# io-board-c-8.net
KiCad netlist of a schematic drawn in EAGLE
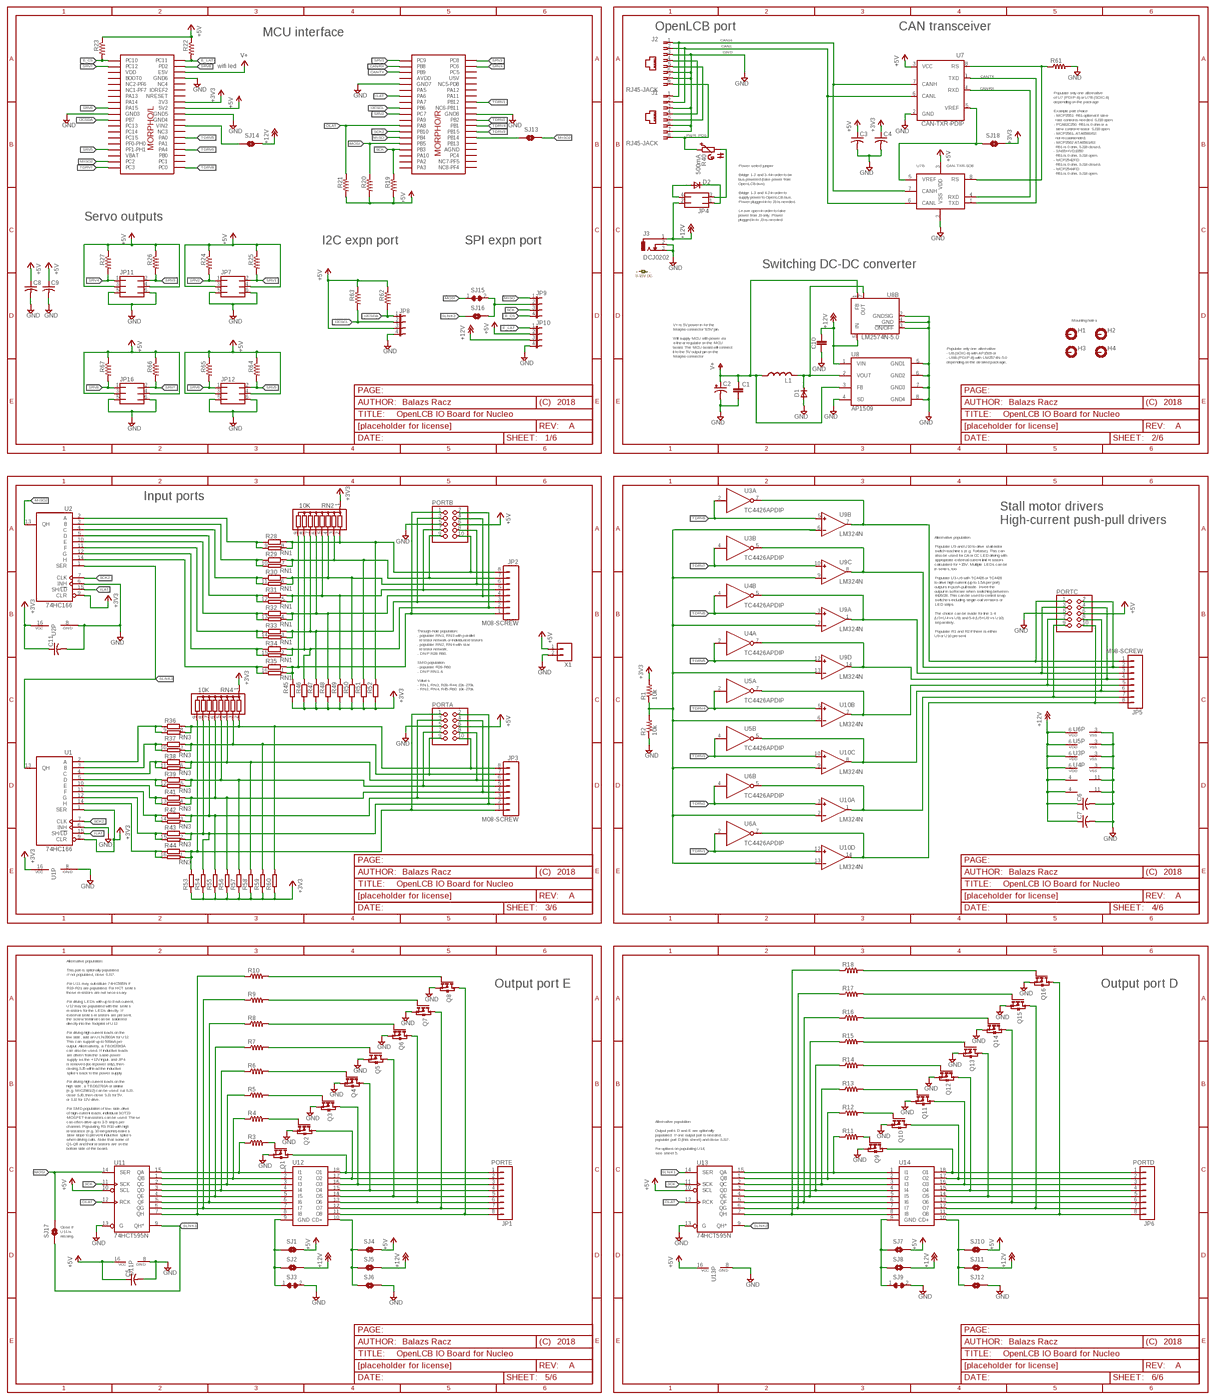
[diagram p0: schematic, sheet 1, overview]
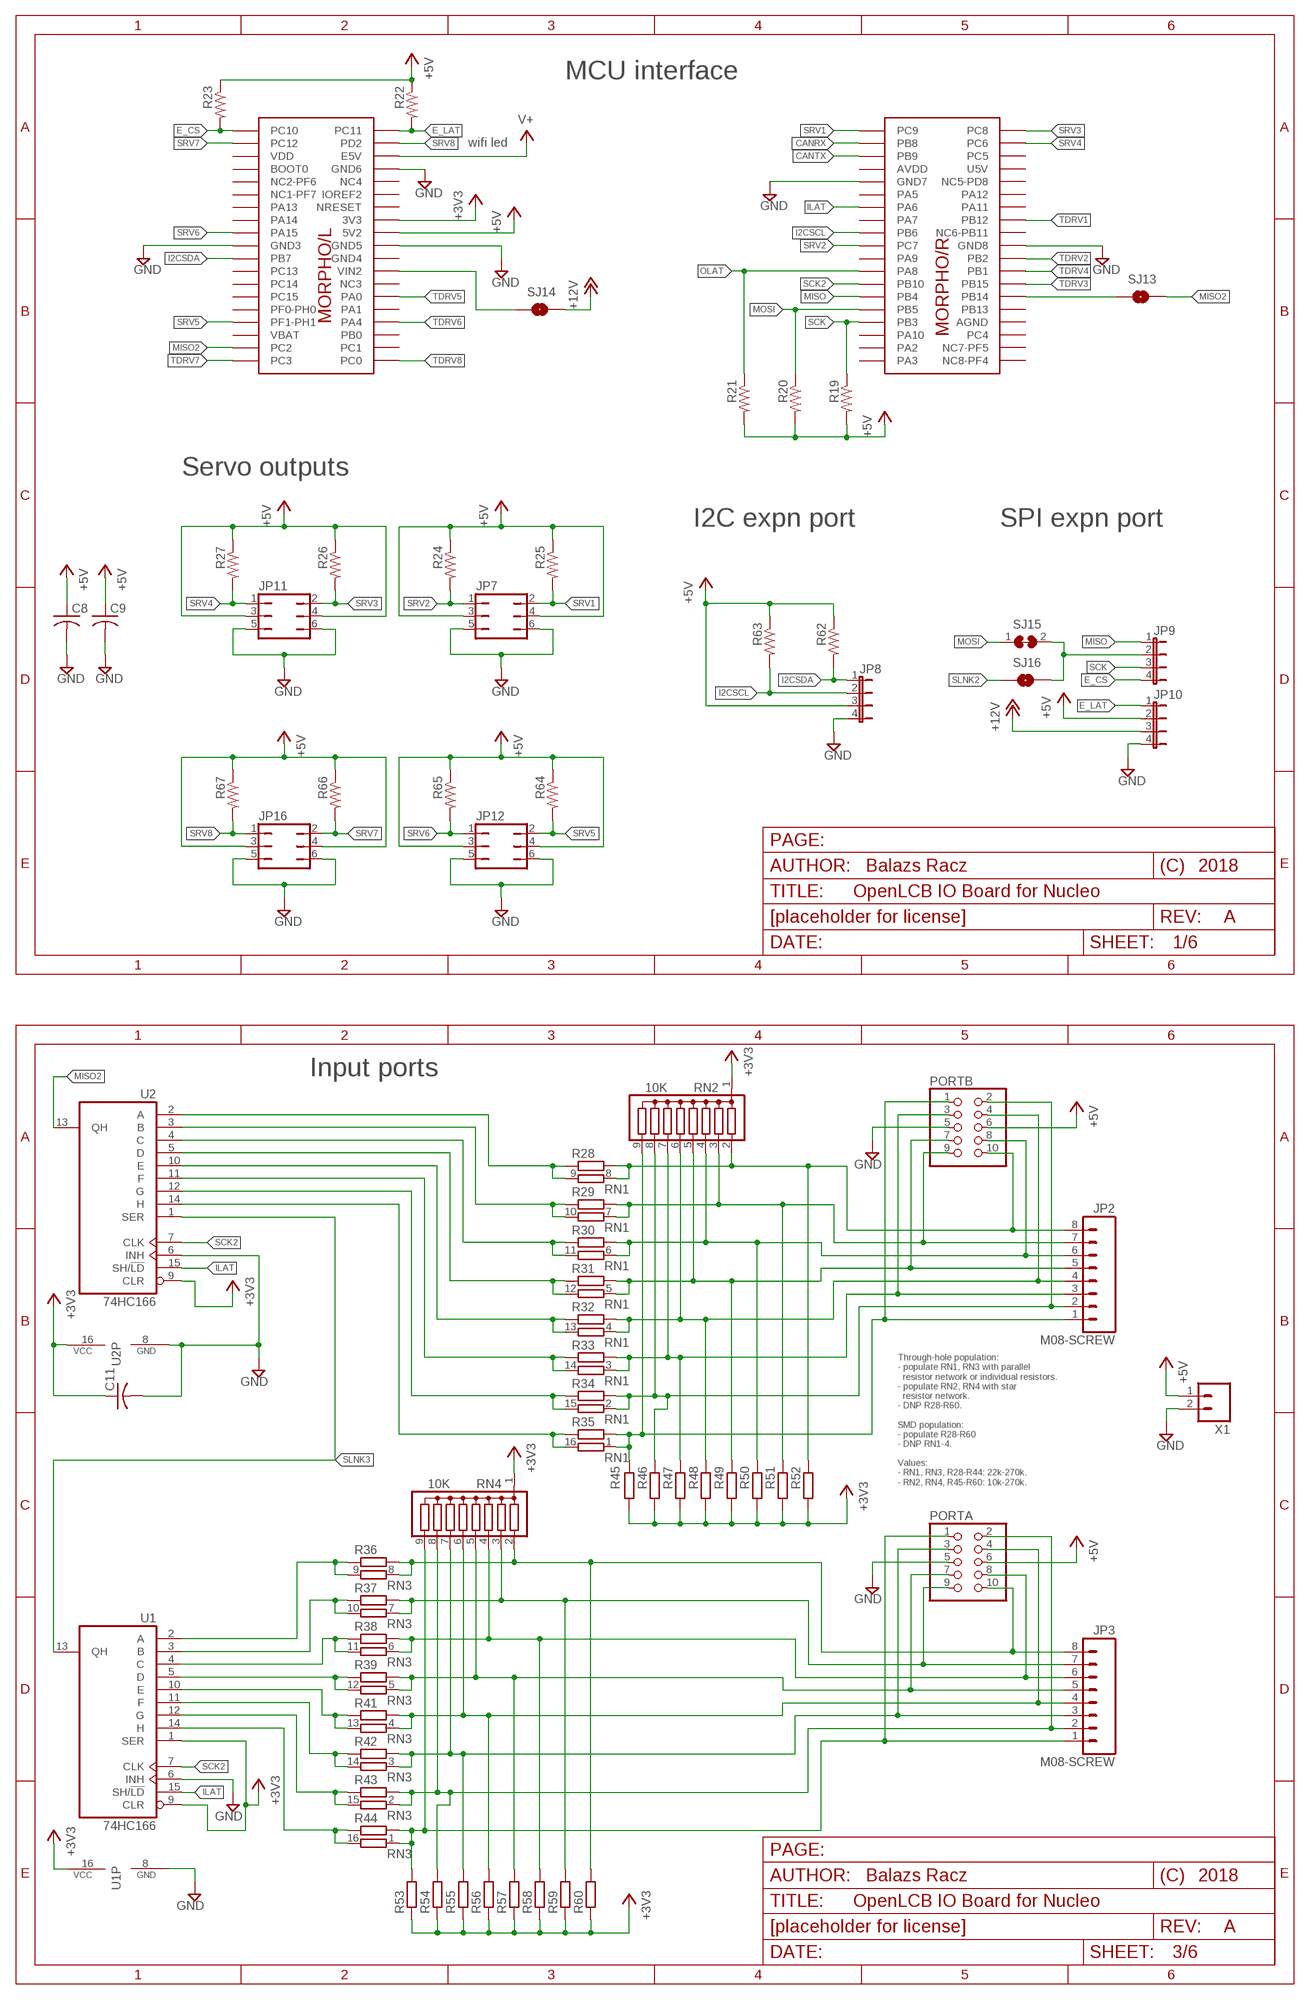
[diagram p1: schematic, sheet 1, part 1 of 4]
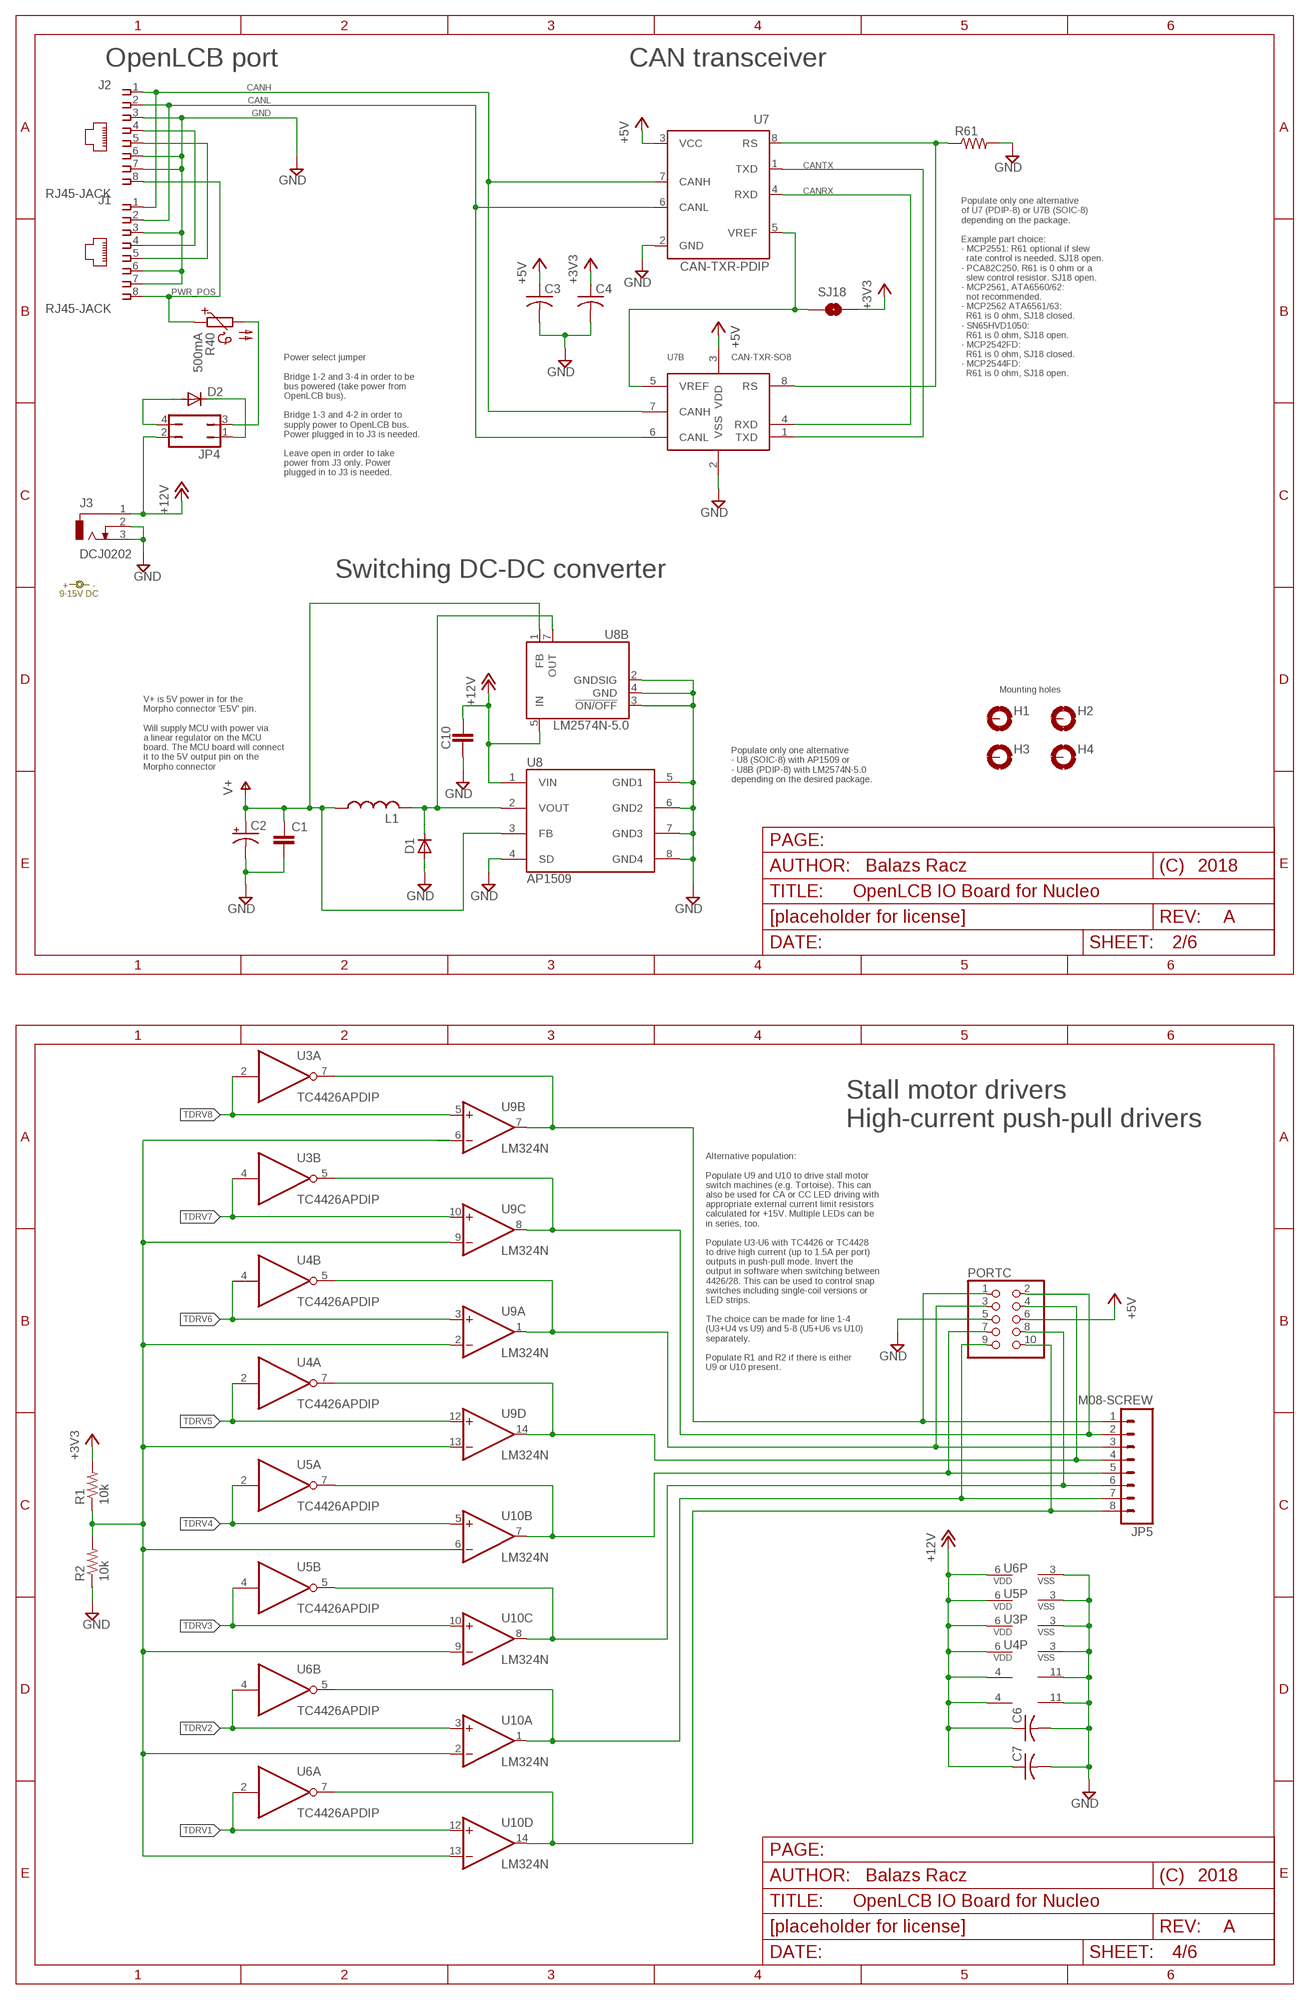
[diagram p2: schematic, sheet 1, part 2 of 4]
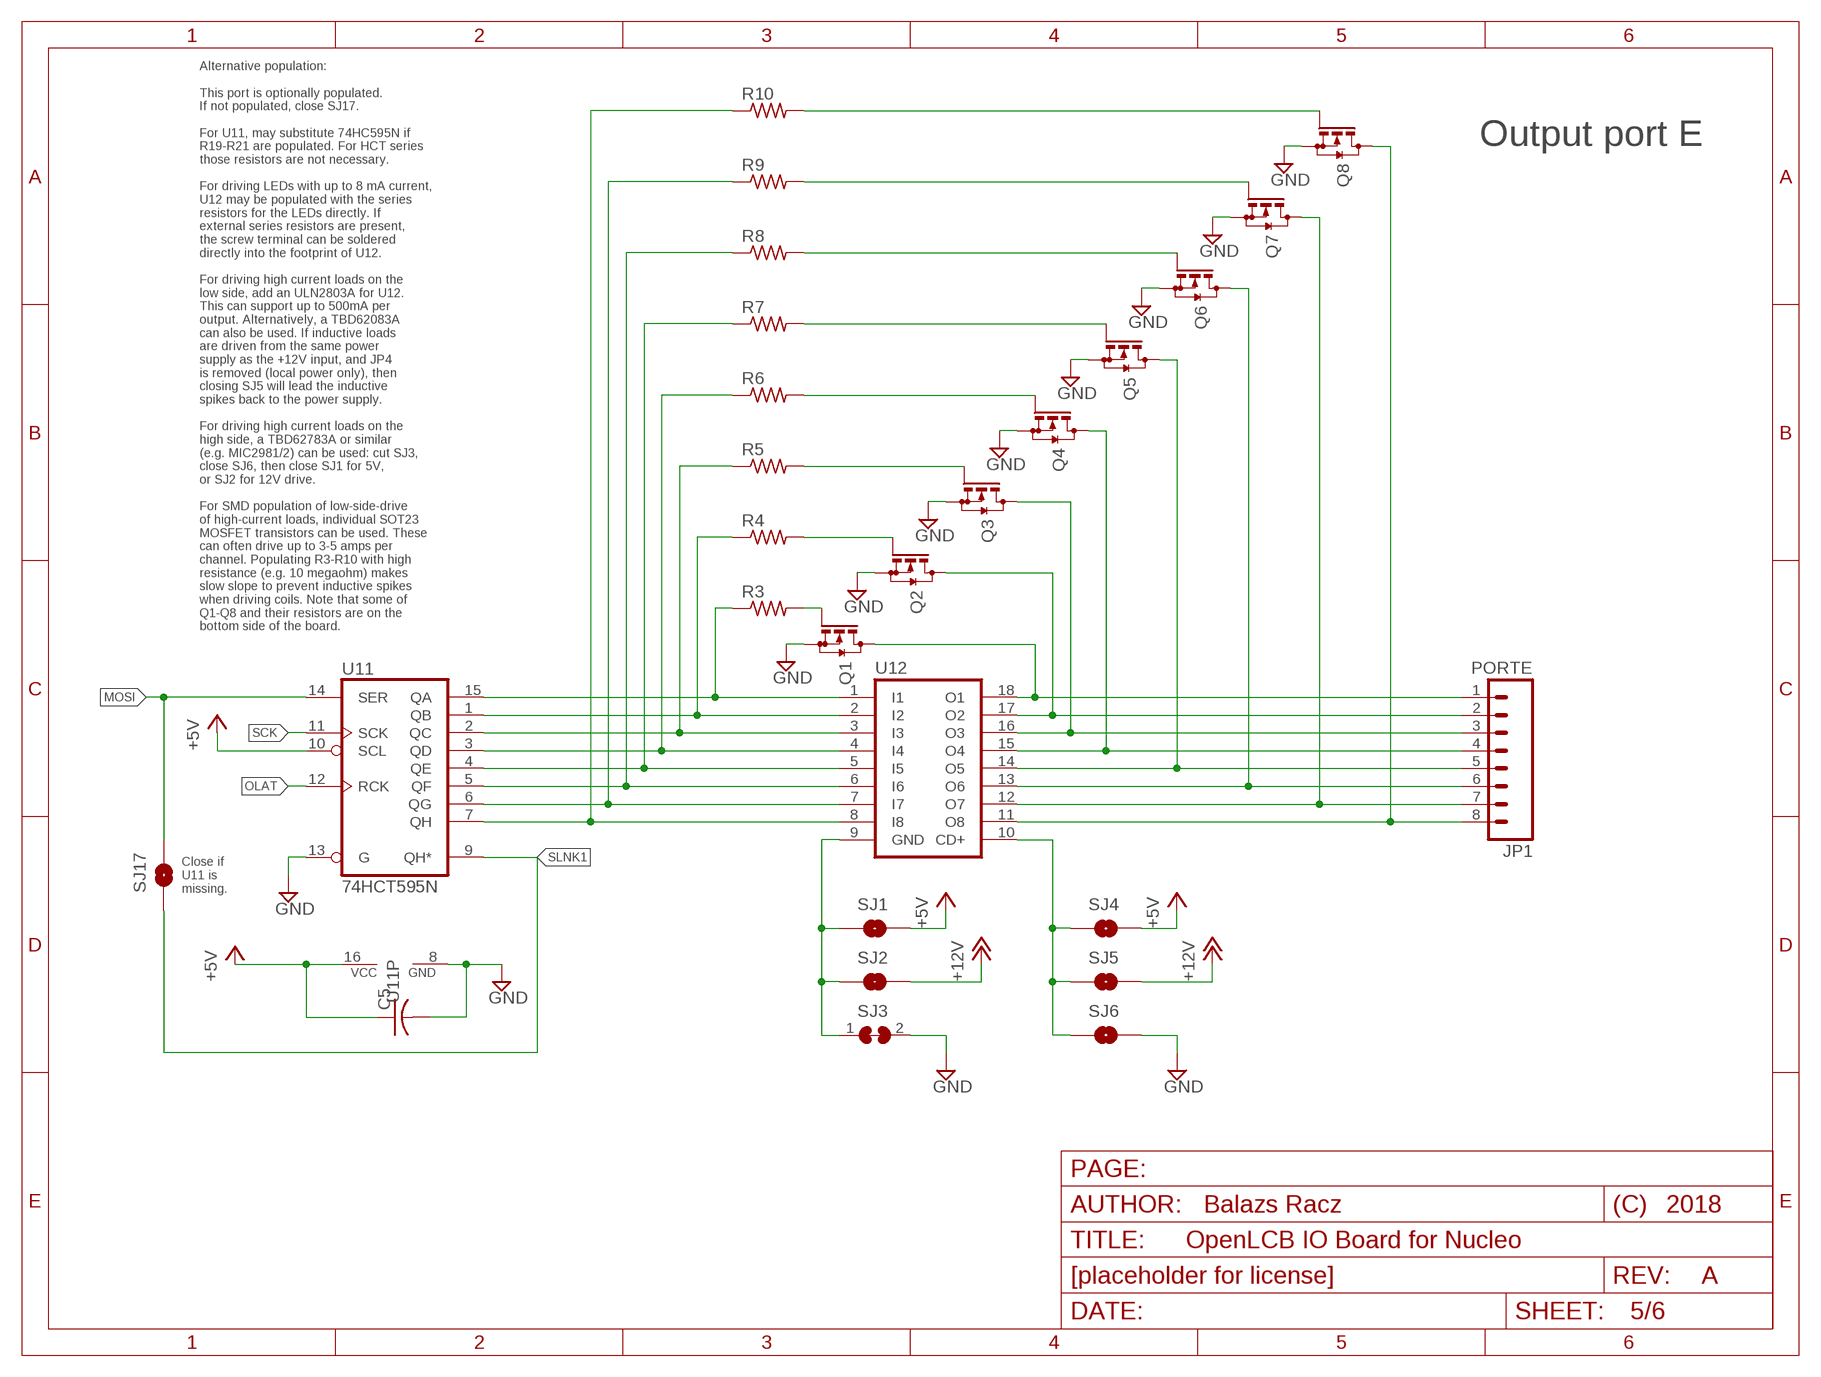
[diagram p3: schematic, sheet 1, part 3 of 4]
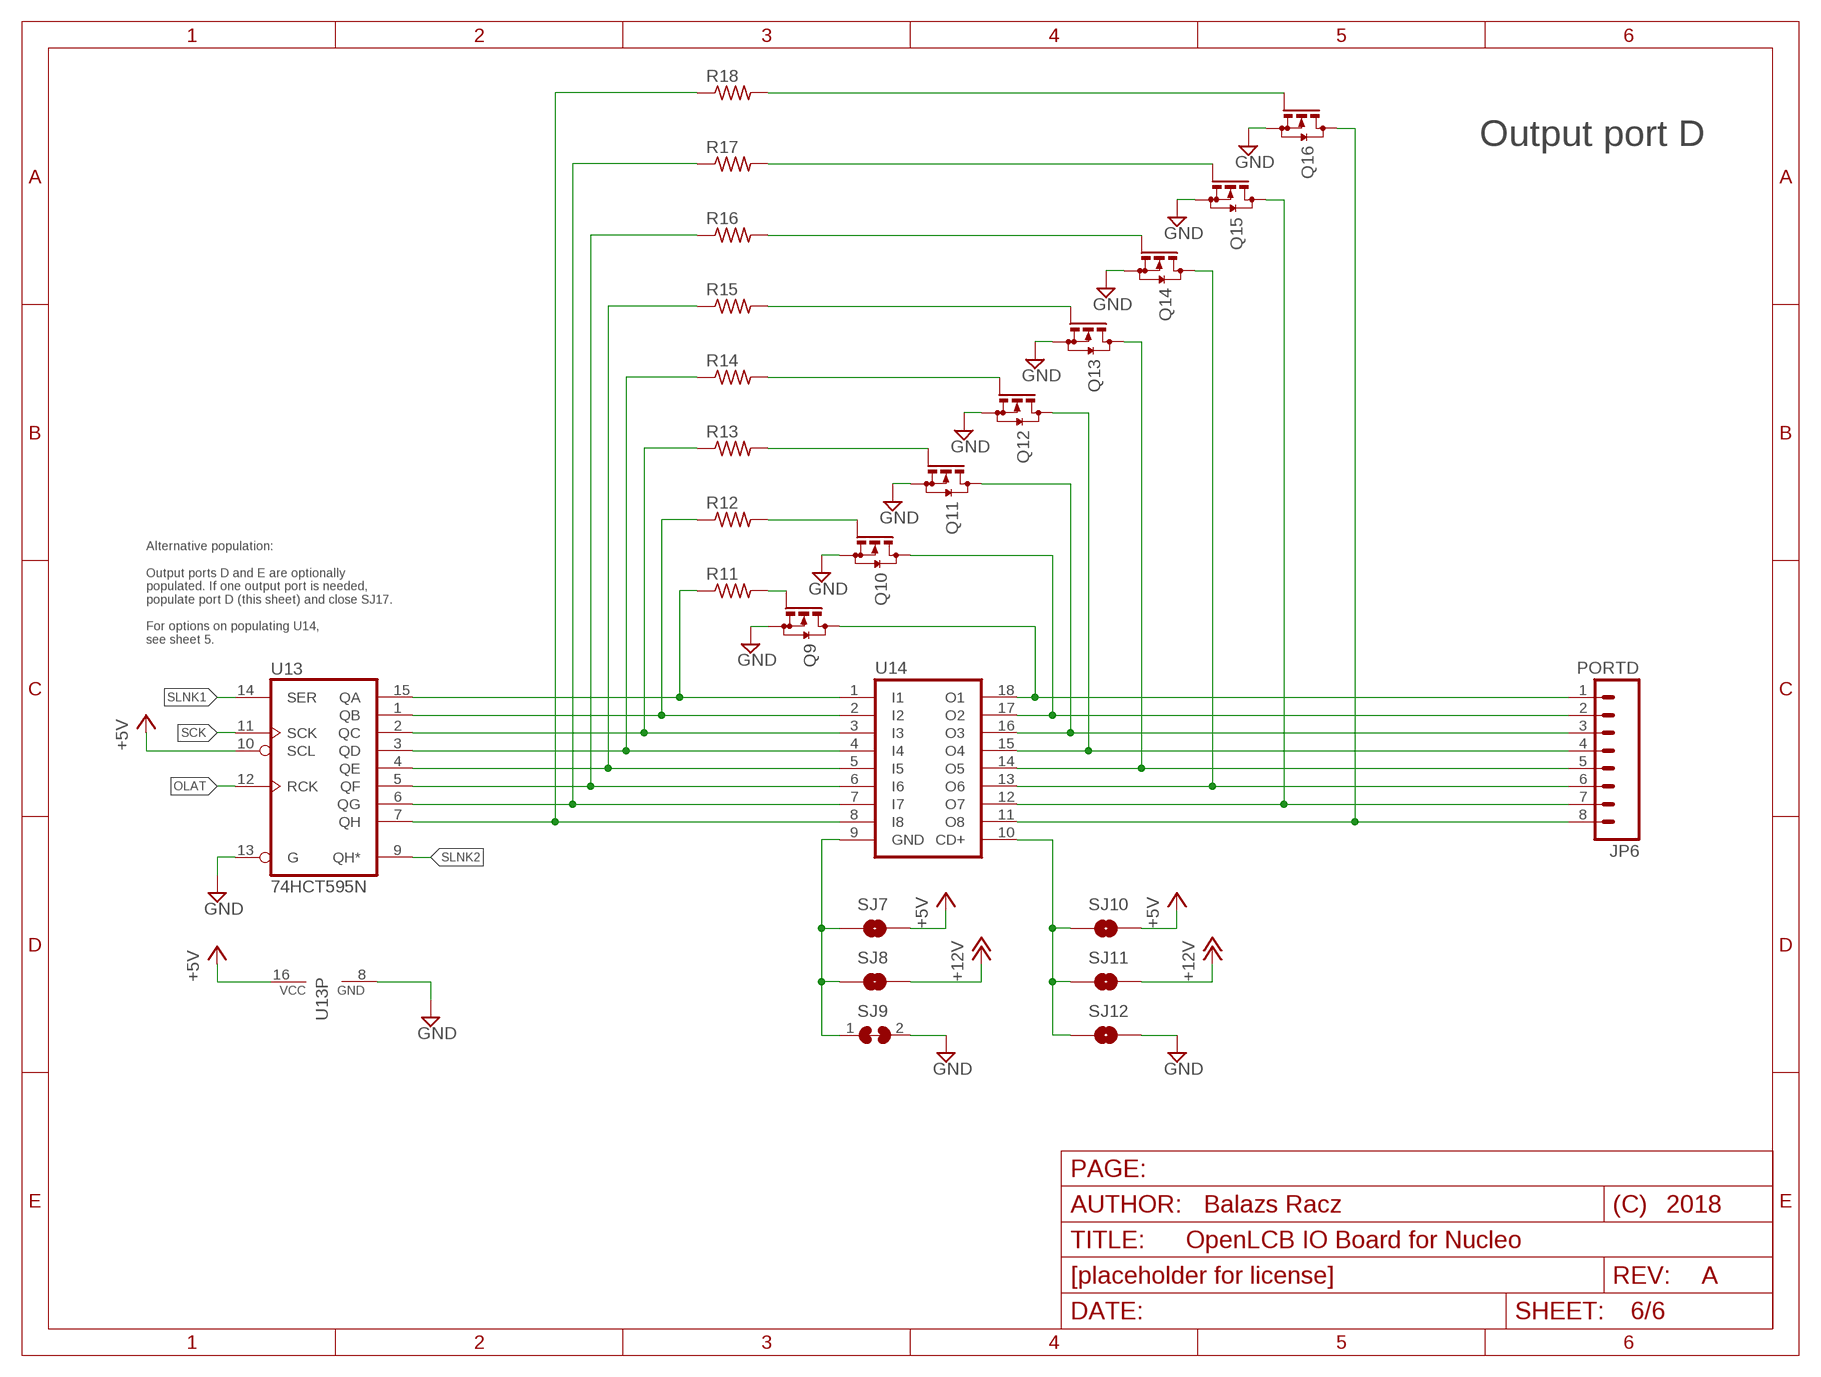
[diagram p4: schematic, sheet 1, part 4 of 4]

(export (version "E")
  (design (tool "Eeschema 10.0.6"))
  (components
    (comp (ref "+12V")
      (value "9-15V DC")
      (footprint "eagle-import:POWER_USAGE")
      (libsource (lib "eagle-import") (part "DOC-POWER_LABEL"))
    )
    (comp (ref "C1")
      (value "C-EUC1206")
      (footprint "eagle-import:C1206")
      (libsource (lib "eagle-import") (part "C-EUC1206"))
    )
    (comp (ref "C2")
      (value "CPOL-USE2.5-5")
      (footprint "eagle-import:E2,5-5")
      (libsource (lib "eagle-import") (part "CPOL-USE2.5-5"))
    )
    (comp (ref "C3")
      (value "C-USC0805")
      (footprint "eagle-import:C0805")
      (libsource (lib "eagle-import") (part "C-USC0805"))
    )
    (comp (ref "C4")
      (value "C-USC0805")
      (footprint "eagle-import:C0805")
      (libsource (lib "eagle-import") (part "C-USC0805"))
    )
    (comp (ref "C5")
      (value "C-USC0805")
      (footprint "eagle-import:C0805")
      (libsource (lib "eagle-import") (part "C-USC0805"))
    )
    (comp (ref "C6")
      (value "C-USC1206")
      (footprint "eagle-import:C1206")
      (libsource (lib "eagle-import") (part "C-USC1206"))
    )
    (comp (ref "C7")
      (value "C-USC1206")
      (footprint "eagle-import:C1206")
      (libsource (lib "eagle-import") (part "C-USC1206"))
    )
    (comp (ref "C8")
      (value "C-USC1206")
      (footprint "eagle-import:C1206")
      (libsource (lib "eagle-import") (part "C-USC1206"))
    )
    (comp (ref "C9")
      (value "C-USC1206")
      (footprint "eagle-import:C1206")
      (libsource (lib "eagle-import") (part "C-USC1206"))
    )
    (comp (ref "C10")
      (value "C-EUC1206")
      (footprint "eagle-import:C1206")
      (libsource (lib "eagle-import") (part "C-EUC1206"))
    )
    (comp (ref "C11")
      (value "C-USC0805")
      (footprint "eagle-import:C0805")
      (libsource (lib "eagle-import") (part "C-USC0805"))
    )
    (comp (ref "D1")
      (value "DIODE-DO41-7.6")
      (footprint "eagle-import:DO41-7.6")
      (libsource (lib "eagle-import") (part "DIODE-DO41-7.6"))
    )
    (comp (ref "D2")
      (value "DIODE-DO41-7.6")
      (footprint "eagle-import:DO41-7.6")
      (libsource (lib "eagle-import") (part "DIODE-DO41-7.6"))
    )
    (comp (ref "H1")
      (value "MOUNT-PAD-ROUND3.3")
      (footprint "eagle-import:3,3-PAD")
      (libsource (lib "eagle-import") (part "MOUNT-PAD-ROUND3.3"))
    )
    (comp (ref "H2")
      (value "MOUNT-PAD-ROUND3.3")
      (footprint "eagle-import:3,3-PAD")
      (libsource (lib "eagle-import") (part "MOUNT-PAD-ROUND3.3"))
    )
    (comp (ref "H3")
      (value "MOUNT-PAD-ROUND3.3")
      (footprint "eagle-import:3,3-PAD")
      (libsource (lib "eagle-import") (part "MOUNT-PAD-ROUND3.3"))
    )
    (comp (ref "H4")
      (value "MOUNT-PAD-ROUND3.3")
      (footprint "eagle-import:3,3-PAD")
      (libsource (lib "eagle-import") (part "MOUNT-PAD-ROUND3.3"))
    )
    (comp (ref "J1")
      (value "RJ45-JACK")
      (footprint "eagle-import:RJ45-PULSE-E5J88")
      (libsource (lib "eagle-import") (part "RJ45-JACKRJ45-PULSE-E5J00"))
    )
    (comp (ref "J2")
      (value "RJ45-JACK")
      (footprint "eagle-import:RJ45-PULSE-E5J88")
      (libsource (lib "eagle-import") (part "RJ45-JACKRJ45-PULSE-E5J00"))
    )
    (comp (ref "J3")
      (value "DCJ0202")
      (footprint "eagle-import:DCJ0202")
      (libsource (lib "eagle-import") (part "DCJ0202"))
    )
    (comp (ref "JP1")
      (value "PORTE")
      (footprint "eagle-import:1X08_TERMINAL")
      (libsource (lib "eagle-import") (part "M08-SCREW"))
    )
    (comp (ref "JP2")
      (value "M08-SCREW")
      (footprint "eagle-import:1X08_TERMINAL")
      (libsource (lib "eagle-import") (part "M08-SCREW"))
    )
    (comp (ref "JP3")
      (value "M08-SCREW")
      (footprint "eagle-import:1X08_TERMINAL")
      (libsource (lib "eagle-import") (part "M08-SCREW"))
    )
    (comp (ref "JP4")
      (value "JP2Q")
      (footprint "eagle-import:JP2Q")
      (libsource (lib "eagle-import") (part "JP2Q"))
    )
    (comp (ref "JP5")
      (value "M08-SCREW")
      (footprint "eagle-import:1X08_TERMINAL")
      (libsource (lib "eagle-import") (part "M08-SCREW"))
    )
    (comp (ref "JP6")
      (value "PORTD")
      (footprint "eagle-import:1X08_TERMINAL")
      (libsource (lib "eagle-import") (part "M08-SCREW"))
    )
    (comp (ref "JP7")
      (value "JP3Q")
      (footprint "eagle-import:JP3Q")
      (libsource (lib "eagle-import") (part "JP3Q"))
    )
    (comp (ref "JP8")
      (value "JP4-FLAT")
      (footprint "eagle-import:JP4F")
      (libsource (lib "eagle-import") (part "JP4-FLAT"))
    )
    (comp (ref "JP9")
      (value "JP4-FLAT")
      (footprint "eagle-import:JP4F")
      (libsource (lib "eagle-import") (part "JP4-FLAT"))
    )
    (comp (ref "JP10")
      (value "JP4-FLAT")
      (footprint "eagle-import:JP4F")
      (libsource (lib "eagle-import") (part "JP4-FLAT"))
    )
    (comp (ref "JP11")
      (value "JP3Q")
      (footprint "eagle-import:JP3Q")
      (libsource (lib "eagle-import") (part "JP3Q"))
    )
    (comp (ref "JP12")
      (value "JP3Q")
      (footprint "eagle-import:JP3Q")
      (libsource (lib "eagle-import") (part "JP3Q"))
    )
    (comp (ref "JP16")
      (value "JP3Q")
      (footprint "eagle-import:JP3Q")
      (libsource (lib "eagle-import") (part "JP3Q"))
    )
    (comp (ref "L1")
      (value "L-US")
      (footprint "eagle-import:L5-8,5")
      (libsource (lib "eagle-import") (part "L-US"))
    )
    (comp (ref "PORTA")
      (value "PINHD-2X5CN")
      (footprint "eagle-import:CON10M")
      (libsource (lib "eagle-import") (part "PINHD-2X5CN"))
    )
    (comp (ref "PORTB")
      (value "PINHD-2X5CN")
      (footprint "eagle-import:CON10M")
      (libsource (lib "eagle-import") (part "PINHD-2X5CN"))
    )
    (comp (ref "PORTC")
      (value "PINHD-2X5CN")
      (footprint "eagle-import:CON10M")
      (libsource (lib "eagle-import") (part "PINHD-2X5CN"))
    )
    (comp (ref "Q1")
      (value "BSS123")
      (footprint "eagle-import:SOT23")
      (libsource (lib "eagle-import") (part "BSS123"))
    )
    (comp (ref "Q2")
      (value "BSS123")
      (footprint "eagle-import:SOT23")
      (libsource (lib "eagle-import") (part "BSS123"))
    )
    (comp (ref "Q3")
      (value "BSS123")
      (footprint "eagle-import:SOT23")
      (libsource (lib "eagle-import") (part "BSS123"))
    )
    (comp (ref "Q4")
      (value "BSS123")
      (footprint "eagle-import:SOT23")
      (libsource (lib "eagle-import") (part "BSS123"))
    )
    (comp (ref "Q5")
      (value "BSS123")
      (footprint "eagle-import:SOT23")
      (libsource (lib "eagle-import") (part "BSS123"))
    )
    (comp (ref "Q6")
      (value "BSS123")
      (footprint "eagle-import:SOT23")
      (libsource (lib "eagle-import") (part "BSS123"))
    )
    (comp (ref "Q7")
      (value "BSS123")
      (footprint "eagle-import:SOT23")
      (libsource (lib "eagle-import") (part "BSS123"))
    )
    (comp (ref "Q8")
      (value "BSS123")
      (footprint "eagle-import:SOT23")
      (libsource (lib "eagle-import") (part "BSS123"))
    )
    (comp (ref "Q9")
      (value "BSS123")
      (footprint "eagle-import:SOT23")
      (libsource (lib "eagle-import") (part "BSS123"))
    )
    (comp (ref "Q10")
      (value "BSS123")
      (footprint "eagle-import:SOT23")
      (libsource (lib "eagle-import") (part "BSS123"))
    )
    (comp (ref "Q11")
      (value "BSS123")
      (footprint "eagle-import:SOT23")
      (libsource (lib "eagle-import") (part "BSS123"))
    )
    (comp (ref "Q12")
      (value "BSS123")
      (footprint "eagle-import:SOT23")
      (libsource (lib "eagle-import") (part "BSS123"))
    )
    (comp (ref "Q13")
      (value "BSS123")
      (footprint "eagle-import:SOT23")
      (libsource (lib "eagle-import") (part "BSS123"))
    )
    (comp (ref "Q14")
      (value "BSS123")
      (footprint "eagle-import:SOT23")
      (libsource (lib "eagle-import") (part "BSS123"))
    )
    (comp (ref "Q15")
      (value "BSS123")
      (footprint "eagle-import:SOT23")
      (libsource (lib "eagle-import") (part "BSS123"))
    )
    (comp (ref "Q16")
      (value "BSS123")
      (footprint "eagle-import:SOT23")
      (libsource (lib "eagle-import") (part "BSS123"))
    )
    (comp (ref "R1")
      (value "10k")
      (footprint "eagle-import:R0805")
      (libsource (lib "eagle-import") (part "R-US_R0805"))
    )
    (comp (ref "R2")
      (value "10k")
      (footprint "eagle-import:R0805")
      (libsource (lib "eagle-import") (part "R-US_R0805"))
    )
    (comp (ref "R3")
      (value "R-US_R0603")
      (footprint "eagle-import:R0603")
      (libsource (lib "eagle-import") (part "R-US_R0603"))
    )
    (comp (ref "R4")
      (value "R-US_R0603")
      (footprint "eagle-import:R0603")
      (libsource (lib "eagle-import") (part "R-US_R0603"))
    )
    (comp (ref "R5")
      (value "R-US_R0603")
      (footprint "eagle-import:R0603")
      (libsource (lib "eagle-import") (part "R-US_R0603"))
    )
    (comp (ref "R6")
      (value "R-US_R0603")
      (footprint "eagle-import:R0603")
      (libsource (lib "eagle-import") (part "R-US_R0603"))
    )
    (comp (ref "R7")
      (value "R-US_R0603")
      (footprint "eagle-import:R0603")
      (libsource (lib "eagle-import") (part "R-US_R0603"))
    )
    (comp (ref "R8")
      (value "R-US_R0603")
      (footprint "eagle-import:R0603")
      (libsource (lib "eagle-import") (part "R-US_R0603"))
    )
    (comp (ref "R9")
      (value "R-US_R0603")
      (footprint "eagle-import:R0603")
      (libsource (lib "eagle-import") (part "R-US_R0603"))
    )
    (comp (ref "R10")
      (value "R-US_R0603")
      (footprint "eagle-import:R0603")
      (libsource (lib "eagle-import") (part "R-US_R0603"))
    )
    (comp (ref "R11")
      (value "R-US_R0603")
      (footprint "eagle-import:R0603")
      (libsource (lib "eagle-import") (part "R-US_R0603"))
    )
    (comp (ref "R12")
      (value "R-US_R0603")
      (footprint "eagle-import:R0603")
      (libsource (lib "eagle-import") (part "R-US_R0603"))
    )
    (comp (ref "R13")
      (value "R-US_R0603")
      (footprint "eagle-import:R0603")
      (libsource (lib "eagle-import") (part "R-US_R0603"))
    )
    (comp (ref "R14")
      (value "R-US_R0603")
      (footprint "eagle-import:R0603")
      (libsource (lib "eagle-import") (part "R-US_R0603"))
    )
    (comp (ref "R15")
      (value "R-US_R0603")
      (footprint "eagle-import:R0603")
      (libsource (lib "eagle-import") (part "R-US_R0603"))
    )
    (comp (ref "R16")
      (value "R-US_R0603")
      (footprint "eagle-import:R0603")
      (libsource (lib "eagle-import") (part "R-US_R0603"))
    )
    (comp (ref "R17")
      (value "R-US_R0603")
      (footprint "eagle-import:R0603")
      (libsource (lib "eagle-import") (part "R-US_R0603"))
    )
    (comp (ref "R18")
      (value "R-US_R0603")
      (footprint "eagle-import:R0603")
      (libsource (lib "eagle-import") (part "R-US_R0603"))
    )
    (comp (ref "R19")
      (value "R-US_R0805")
      (footprint "eagle-import:R0805")
      (libsource (lib "eagle-import") (part "rcl_334_R-US_R0805"))
    )
    (comp (ref "R20")
      (value "R-US_R0805")
      (footprint "eagle-import:R0805")
      (libsource (lib "eagle-import") (part "rcl_334_R-US_R0805"))
    )
    (comp (ref "R21")
      (value "R-US_R0805")
      (footprint "eagle-import:R0805")
      (libsource (lib "eagle-import") (part "rcl_334_R-US_R0805"))
    )
    (comp (ref "R22")
      (value "R-US_R0805")
      (footprint "eagle-import:R0805")
      (libsource (lib "eagle-import") (part "rcl_334_R-US_R0805"))
    )
    (comp (ref "R23")
      (value "R-US_R0805")
      (footprint "eagle-import:R0805")
      (libsource (lib "eagle-import") (part "rcl_334_R-US_R0805"))
    )
    (comp (ref "R24")
      (value "R-US_R0805")
      (footprint "eagle-import:R0805")
      (libsource (lib "eagle-import") (part "rcl_334_R-US_R0805"))
    )
    (comp (ref "R25")
      (value "R-US_R0805")
      (footprint "eagle-import:R0805")
      (libsource (lib "eagle-import") (part "rcl_334_R-US_R0805"))
    )
    (comp (ref "R26")
      (value "R-US_R0805")
      (footprint "eagle-import:R0805")
      (libsource (lib "eagle-import") (part "rcl_334_R-US_R0805"))
    )
    (comp (ref "R27")
      (value "R-US_R0805")
      (footprint "eagle-import:R0805")
      (libsource (lib "eagle-import") (part "rcl_334_R-US_R0805"))
    )
    (comp (ref "R28")
      (value "R-EU_R0603")
      (footprint "eagle-import:R0603")
      (libsource (lib "eagle-import") (part "R-EU_R0603"))
    )
    (comp (ref "R29")
      (value "R-EU_R0603")
      (footprint "eagle-import:R0603")
      (libsource (lib "eagle-import") (part "R-EU_R0603"))
    )
    (comp (ref "R30")
      (value "R-EU_R0603")
      (footprint "eagle-import:R0603")
      (libsource (lib "eagle-import") (part "R-EU_R0603"))
    )
    (comp (ref "R31")
      (value "R-EU_R0603")
      (footprint "eagle-import:R0603")
      (libsource (lib "eagle-import") (part "R-EU_R0603"))
    )
    (comp (ref "R32")
      (value "R-EU_R0603")
      (footprint "eagle-import:R0603")
      (libsource (lib "eagle-import") (part "R-EU_R0603"))
    )
    (comp (ref "R33")
      (value "R-EU_R0603")
      (footprint "eagle-import:R0603")
      (libsource (lib "eagle-import") (part "R-EU_R0603"))
    )
    (comp (ref "R34")
      (value "R-EU_R0603")
      (footprint "eagle-import:R0603")
      (libsource (lib "eagle-import") (part "R-EU_R0603"))
    )
    (comp (ref "R35")
      (value "R-EU_R0603")
      (footprint "eagle-import:R0603")
      (libsource (lib "eagle-import") (part "R-EU_R0603"))
    )
    (comp (ref "R36")
      (value "R-EU_R0603")
      (footprint "eagle-import:R0603")
      (libsource (lib "eagle-import") (part "R-EU_R0603"))
    )
    (comp (ref "R37")
      (value "R-EU_R0603")
      (footprint "eagle-import:R0603")
      (libsource (lib "eagle-import") (part "R-EU_R0603"))
    )
    (comp (ref "R38")
      (value "R-EU_R0603")
      (footprint "eagle-import:R0603")
      (libsource (lib "eagle-import") (part "R-EU_R0603"))
    )
    (comp (ref "R39")
      (value "R-EU_R0603")
      (footprint "eagle-import:R0603")
      (libsource (lib "eagle-import") (part "R-EU_R0603"))
    )
    (comp (ref "R40")
      (value "500mA")
      (footprint "eagle-import:PTC1812")
      (libsource (lib "eagle-import") (part "PTC_1812"))
    )
    (comp (ref "R41")
      (value "R-EU_R0603")
      (footprint "eagle-import:R0603")
      (libsource (lib "eagle-import") (part "R-EU_R0603"))
    )
    (comp (ref "R42")
      (value "R-EU_R0603")
      (footprint "eagle-import:R0603")
      (libsource (lib "eagle-import") (part "R-EU_R0603"))
    )
    (comp (ref "R43")
      (value "R-EU_R0603")
      (footprint "eagle-import:R0603")
      (libsource (lib "eagle-import") (part "R-EU_R0603"))
    )
    (comp (ref "R44")
      (value "R-EU_R0603")
      (footprint "eagle-import:R0603")
      (libsource (lib "eagle-import") (part "R-EU_R0603"))
    )
    (comp (ref "R45")
      (value "R-EU_R0603")
      (footprint "eagle-import:R0603")
      (libsource (lib "eagle-import") (part "R-EU_R0603"))
    )
    (comp (ref "R46")
      (value "R-EU_R0603")
      (footprint "eagle-import:R0603")
      (libsource (lib "eagle-import") (part "R-EU_R0603"))
    )
    (comp (ref "R47")
      (value "R-EU_R0603")
      (footprint "eagle-import:R0603")
      (libsource (lib "eagle-import") (part "R-EU_R0603"))
    )
    (comp (ref "R48")
      (value "R-EU_R0603")
      (footprint "eagle-import:R0603")
      (libsource (lib "eagle-import") (part "R-EU_R0603"))
    )
    (comp (ref "R49")
      (value "R-EU_R0603")
      (footprint "eagle-import:R0603")
      (libsource (lib "eagle-import") (part "R-EU_R0603"))
    )
    (comp (ref "R50")
      (value "R-EU_R0603")
      (footprint "eagle-import:R0603")
      (libsource (lib "eagle-import") (part "R-EU_R0603"))
    )
    (comp (ref "R51")
      (value "R-EU_R0603")
      (footprint "eagle-import:R0603")
      (libsource (lib "eagle-import") (part "R-EU_R0603"))
    )
    (comp (ref "R52")
      (value "R-EU_R0603")
      (footprint "eagle-import:R0603")
      (libsource (lib "eagle-import") (part "R-EU_R0603"))
    )
    (comp (ref "R53")
      (value "R-EU_R0603")
      (footprint "eagle-import:R0603")
      (libsource (lib "eagle-import") (part "R-EU_R0603"))
    )
    (comp (ref "R54")
      (value "R-EU_R0603")
      (footprint "eagle-import:R0603")
      (libsource (lib "eagle-import") (part "R-EU_R0603"))
    )
    (comp (ref "R55")
      (value "R-EU_R0603")
      (footprint "eagle-import:R0603")
      (libsource (lib "eagle-import") (part "R-EU_R0603"))
    )
    (comp (ref "R56")
      (value "R-EU_R0603")
      (footprint "eagle-import:R0603")
      (libsource (lib "eagle-import") (part "R-EU_R0603"))
    )
    (comp (ref "R57")
      (value "R-EU_R0603")
      (footprint "eagle-import:R0603")
      (libsource (lib "eagle-import") (part "R-EU_R0603"))
    )
    (comp (ref "R58")
      (value "R-EU_R0603")
      (footprint "eagle-import:R0603")
      (libsource (lib "eagle-import") (part "R-EU_R0603"))
    )
    (comp (ref "R59")
      (value "R-EU_R0603")
      (footprint "eagle-import:R0603")
      (libsource (lib "eagle-import") (part "R-EU_R0603"))
    )
    (comp (ref "R60")
      (value "R-EU_R0603")
      (footprint "eagle-import:R0603")
      (libsource (lib "eagle-import") (part "R-EU_R0603"))
    )
    (comp (ref "R61")
      (value "R-US_R0805")
      (footprint "eagle-import:R0805")
      (libsource (lib "eagle-import") (part "rcl_334_R-US_R0805"))
    )
    (comp (ref "R62")
      (value "R-US_R0805")
      (footprint "eagle-import:R0805")
      (libsource (lib "eagle-import") (part "rcl_334_R-US_R0805"))
    )
    (comp (ref "R63")
      (value "R-US_R0805")
      (footprint "eagle-import:R0805")
      (libsource (lib "eagle-import") (part "rcl_334_R-US_R0805"))
    )
    (comp (ref "R64")
      (value "R-US_R0805")
      (footprint "eagle-import:R0805")
      (libsource (lib "eagle-import") (part "rcl_334_R-US_R0805"))
    )
    (comp (ref "R65")
      (value "R-US_R0805")
      (footprint "eagle-import:R0805")
      (libsource (lib "eagle-import") (part "rcl_334_R-US_R0805"))
    )
    (comp (ref "R66")
      (value "R-US_R0805")
      (footprint "eagle-import:R0805")
      (libsource (lib "eagle-import") (part "rcl_334_R-US_R0805"))
    )
    (comp (ref "R67")
      (value "R-US_R0805")
      (footprint "eagle-import:R0805")
      (libsource (lib "eagle-import") (part "rcl_334_R-US_R0805"))
    )
    (comp (ref "RN1")
      (value "8R-P")
      (footprint "eagle-import:DIL16")
      (libsource (lib "eagle-import") (part "8R-P"))
    )
    (comp (ref "RN2")
      (value "10K")
      (footprint "eagle-import:SIL9")
      (libsource (lib "eagle-import") (part "G08R"))
    )
    (comp (ref "RN3")
      (value "8R-P")
      (footprint "eagle-import:DIL16")
      (libsource (lib "eagle-import") (part "8R-P"))
    )
    (comp (ref "RN4")
      (value "10K")
      (footprint "eagle-import:SIL9")
      (libsource (lib "eagle-import") (part "G08R"))
    )
    (comp (ref "SJ1")
      (value "SJRND2")
      (footprint "eagle-import:SJ_RND2")
      (libsource (lib "eagle-import") (part "SJRND2"))
    )
    (comp (ref "SJ2")
      (value "SJRND2")
      (footprint "eagle-import:SJ_RND2")
      (libsource (lib "eagle-import") (part "SJRND2"))
    )
    (comp (ref "SJ3")
      (value "SJ-C")
      (footprint "eagle-import:SJW-C")
      (libsource (lib "eagle-import") (part "SJ-C"))
    )
    (comp (ref "SJ4")
      (value "SJRND2")
      (footprint "eagle-import:SJ_RND2")
      (libsource (lib "eagle-import") (part "SJRND2"))
    )
    (comp (ref "SJ5")
      (value "SJRND2")
      (footprint "eagle-import:SJ_RND2")
      (libsource (lib "eagle-import") (part "SJRND2"))
    )
    (comp (ref "SJ6")
      (value "SJRND2")
      (footprint "eagle-import:SJ_RND2")
      (libsource (lib "eagle-import") (part "SJRND2"))
    )
    (comp (ref "SJ7")
      (value "SJRND2")
      (footprint "eagle-import:SJ_RND2")
      (libsource (lib "eagle-import") (part "SJRND2"))
    )
    (comp (ref "SJ8")
      (value "SJRND2")
      (footprint "eagle-import:SJ_RND2")
      (libsource (lib "eagle-import") (part "SJRND2"))
    )
    (comp (ref "SJ9")
      (value "SJ-C")
      (footprint "eagle-import:SJW-C")
      (libsource (lib "eagle-import") (part "SJ-C"))
    )
    (comp (ref "SJ10")
      (value "SJRND2")
      (footprint "eagle-import:SJ_RND2")
      (libsource (lib "eagle-import") (part "SJRND2"))
    )
    (comp (ref "SJ11")
      (value "SJRND2")
      (footprint "eagle-import:SJ_RND2")
      (libsource (lib "eagle-import") (part "SJRND2"))
    )
    (comp (ref "SJ12")
      (value "SJRND2")
      (footprint "eagle-import:SJ_RND2")
      (libsource (lib "eagle-import") (part "SJRND2"))
    )
    (comp (ref "SJ13")
      (value "SJRND2")
      (footprint "eagle-import:SJ_RND2")
      (libsource (lib "eagle-import") (part "SJRND2"))
    )
    (comp (ref "SJ14")
      (value "SJRND2")
      (footprint "eagle-import:SJ_RND2")
      (libsource (lib "eagle-import") (part "SJRND2"))
    )
    (comp (ref "SJ15")
      (value "SJ-C")
      (footprint "eagle-import:SJW-C")
      (libsource (lib "eagle-import") (part "SJ-C"))
    )
    (comp (ref "SJ16")
      (value "SJRND2")
      (footprint "eagle-import:SJ_RND2")
      (libsource (lib "eagle-import") (part "SJRND2"))
    )
    (comp (ref "SJ17")
      (value "SJRND2")
      (footprint "eagle-import:SJ_RND2")
      (libsource (lib "eagle-import") (part "SJRND2"))
    )
    (comp (ref "SJ18")
      (value "SJRND2")
      (footprint "eagle-import:SJ_RND2")
      (libsource (lib "eagle-import") (part "SJRND2"))
    )
    (comp (ref "U$1")
      (value "NUCLEO_64_GENERIC")
      (footprint "eagle-import:NUCLEO_BRD_BASE64")
      (libsource (lib "eagle-import") (part "NUCLEO_64_GENERIC"))
    )
    (comp (ref "U1")
      (value "74HC166")
      (footprint "eagle-import:DIL16")
      (libsource (lib "eagle-import") (part "74166N"))
    )
    (comp (ref "U2")
      (value "74HC166")
      (footprint "eagle-import:DIL16")
      (libsource (lib "eagle-import") (part "74166N"))
    )
    (comp (ref "U3")
      (value "TC4426APDIP")
      (footprint "eagle-import:DIL08-LONG")
      (libsource (lib "eagle-import") (part "TC4426APDIP"))
    )
    (comp (ref "U4")
      (value "TC4426APDIP")
      (footprint "eagle-import:DIL08-LONG")
      (libsource (lib "eagle-import") (part "TC4426APDIP"))
    )
    (comp (ref "U5")
      (value "TC4426APDIP")
      (footprint "eagle-import:DIL08-LONG")
      (libsource (lib "eagle-import") (part "TC4426APDIP"))
    )
    (comp (ref "U6")
      (value "TC4426APDIP")
      (footprint "eagle-import:DIL08-LONG")
      (libsource (lib "eagle-import") (part "TC4426APDIP"))
    )
    (comp (ref "U7")
      (value "CAN-TXR-PDIP")
      (footprint "eagle-import:DIL08")
      (libsource (lib "eagle-import") (part "PCA82C250"))
    )
    (comp (ref "U7B")
      (value "CAN-TXR-SO8")
      (footprint "eagle-import:SO-08")
      (libsource (lib "eagle-import") (part "MCP2551-SN"))
    )
    (comp (ref "U8")
      (value "AP1509")
      (footprint "eagle-import:SO-08")
      (libsource (lib "eagle-import") (part "AP1509"))
    )
    (comp (ref "U8B")
      (value "LM2574N-5.0")
      (footprint "eagle-import:DIL08")
      (libsource (lib "eagle-import") (part "LM2574?-N5.0"))
    )
    (comp (ref "U9")
      (value "LM324N")
      (footprint "eagle-import:DIL14")
      (libsource (lib "eagle-import") (part "LM324N"))
    )
    (comp (ref "U10")
      (value "LM324N")
      (footprint "eagle-import:DIL14")
      (libsource (lib "eagle-import") (part "LM324N"))
    )
    (comp (ref "U11")
      (value "74HCT595N")
      (footprint "eagle-import:DIL16")
      (libsource (lib "eagle-import") (part "74595NHCT"))
    )
    (comp (ref "U12")
      (value "ULN2803A")
      (footprint "eagle-import:DIL18-THIN")
      (libsource (lib "eagle-import") (part "ULN2803A"))
    )
    (comp (ref "U13")
      (value "74HCT595N")
      (footprint "eagle-import:DIL16")
      (libsource (lib "eagle-import") (part "74595NHCT"))
    )
    (comp (ref "U14")
      (value "ULN2803A")
      (footprint "eagle-import:DIL18-THIN")
      (libsource (lib "eagle-import") (part "ULN2803A"))
    )
    (comp (ref "X1")
      (value "CONNECTOR-M023.5MM-LOCK")
      (footprint "eagle-import:SCREWTERMINAL-3.5MM-2_LOCK")
      (libsource (lib "eagle-import") (part "CONNECTOR-M023.5MM-LOCK"))
    )
  )
  (nets
    (net (code "1") (name "+3V3") (class "Default")
      (node (ref "C11") (pin "1") (pinfunction "1_1") (pintype "passive"))
      (node (ref "C4") (pin "1") (pinfunction "1_1") (pintype "passive"))
      (node (ref "R1") (pin "2") (pinfunction "2_2") (pintype "passive"))
      (node (ref "R45") (pin "1") (pinfunction "1_1") (pintype "passive"))
      (node (ref "R46") (pin "2") (pinfunction "2_2") (pintype "passive"))
      (node (ref "R47") (pin "2") (pinfunction "2_2") (pintype "passive"))
      (node (ref "R48") (pin "2") (pinfunction "2_2") (pintype "passive"))
      (node (ref "R49") (pin "2") (pinfunction "2_2") (pintype "passive"))
      (node (ref "R50") (pin "2") (pinfunction "2_2") (pintype "passive"))
      (node (ref "R51") (pin "2") (pinfunction "2_2") (pintype "passive"))
      (node (ref "R52") (pin "2") (pinfunction "2_2") (pintype "passive"))
      (node (ref "R53") (pin "1") (pinfunction "1_1") (pintype "passive"))
      (node (ref "R54") (pin "1") (pinfunction "1_1") (pintype "passive"))
      (node (ref "R55") (pin "1") (pinfunction "1_1") (pintype "passive"))
      (node (ref "R56") (pin "1") (pinfunction "1_1") (pintype "passive"))
      (node (ref "R57") (pin "1") (pinfunction "1_1") (pintype "passive"))
      (node (ref "R58") (pin "1") (pinfunction "1_1") (pintype "passive"))
      (node (ref "R59") (pin "1") (pinfunction "1_1") (pintype "passive"))
      (node (ref "R60") (pin "1") (pinfunction "1_1") (pintype "passive"))
      (node (ref "RN2") (pin "1") (pinfunction "1_1") (pintype "passive"))
      (node (ref "RN4") (pin "1") (pinfunction "1_1") (pintype "passive"))
      (node (ref "SJ18") (pin "P$1") (pinfunction "1_P$1") (pintype "passive"))
      (node (ref "U$1") (pin "3V3") (pinfunction "3V3_3V3") (pintype "power_in"))
      (node (ref "U1") (pin "1") (pinfunction "SER_1") (pintype "input"))
      (node (ref "U1") (pin "16") (pinfunction "VCC_16") (pintype "power_in"))
      (node (ref "U1") (pin "9") (pinfunction "CLR_9") (pintype "input"))
      (node (ref "U2") (pin "16") (pinfunction "VCC_16") (pintype "power_in"))
      (node (ref "U2") (pin "9") (pinfunction "CLR_9") (pintype "input"))
    )
    (net (code "2") (name "+5V") (class "Default")
      (node (ref "C3") (pin "1") (pinfunction "1_1") (pintype "passive"))
      (node (ref "C5") (pin "1") (pinfunction "1_1") (pintype "passive"))
      (node (ref "C8") (pin "1") (pinfunction "1_1") (pintype "passive"))
      (node (ref "C9") (pin "1") (pinfunction "1_1") (pintype "passive"))
      (node (ref "JP10") (pin "2") (pinfunction "2_2") (pintype "passive"))
      (node (ref "JP11") (pin "3") (pinfunction "3_3") (pintype "passive"))
      (node (ref "JP11") (pin "4") (pinfunction "4_4") (pintype "passive"))
      (node (ref "JP12") (pin "3") (pinfunction "3_3") (pintype "passive"))
      (node (ref "JP12") (pin "4") (pinfunction "4_4") (pintype "passive"))
      (node (ref "JP16") (pin "3") (pinfunction "3_3") (pintype "passive"))
      (node (ref "JP16") (pin "4") (pinfunction "4_4") (pintype "passive"))
      (node (ref "JP7") (pin "3") (pinfunction "3_3") (pintype "passive"))
      (node (ref "JP7") (pin "4") (pinfunction "4_4") (pintype "passive"))
      (node (ref "JP8") (pin "3") (pinfunction "3_3") (pintype "passive"))
      (node (ref "PORTA") (pin "6") (pinfunction "6_6") (pintype "passive"))
      (node (ref "PORTB") (pin "6") (pinfunction "6_6") (pintype "passive"))
      (node (ref "PORTC") (pin "6") (pinfunction "6_6") (pintype "passive"))
      (node (ref "R19") (pin "2") (pinfunction "2_2") (pintype "passive"))
      (node (ref "R20") (pin "2") (pinfunction "2_2") (pintype "passive"))
      (node (ref "R21") (pin "2") (pinfunction "2_2") (pintype "passive"))
      (node (ref "R22") (pin "1") (pinfunction "1_1") (pintype "passive"))
      (node (ref "R23") (pin "1") (pinfunction "1_1") (pintype "passive"))
      (node (ref "R24") (pin "1") (pinfunction "1_1") (pintype "passive"))
      (node (ref "R25") (pin "1") (pinfunction "1_1") (pintype "passive"))
      (node (ref "R26") (pin "1") (pinfunction "1_1") (pintype "passive"))
      (node (ref "R27") (pin "1") (pinfunction "1_1") (pintype "passive"))
      (node (ref "R62") (pin "1") (pinfunction "1_1") (pintype "passive"))
      (node (ref "R63") (pin "1") (pinfunction "1_1") (pintype "passive"))
      (node (ref "R64") (pin "1") (pinfunction "1_1") (pintype "passive"))
      (node (ref "R65") (pin "1") (pinfunction "1_1") (pintype "passive"))
      (node (ref "R66") (pin "1") (pinfunction "1_1") (pintype "passive"))
      (node (ref "R67") (pin "1") (pinfunction "1_1") (pintype "passive"))
      (node (ref "SJ1") (pin "P$2") (pinfunction "2_P$2") (pintype "passive"))
      (node (ref "SJ10") (pin "P$2") (pinfunction "2_P$2") (pintype "passive"))
      (node (ref "SJ4") (pin "P$2") (pinfunction "2_P$2") (pintype "passive"))
      (node (ref "SJ7") (pin "P$2") (pinfunction "2_P$2") (pintype "passive"))
      (node (ref "U$1") (pin "5V2") (pinfunction "5V2_5V2") (pintype "power_in"))
      (node (ref "U11") (pin "10") (pinfunction "SCL_10") (pintype "input"))
      (node (ref "U11") (pin "16") (pinfunction "VCC_16") (pintype "power_in"))
      (node (ref "U13") (pin "10") (pinfunction "SCL_10") (pintype "input"))
      (node (ref "U13") (pin "16") (pinfunction "VCC_16") (pintype "power_in"))
      (node (ref "U7") (pin "3") (pinfunction "VCC_3") (pintype "power_in"))
      (node (ref "U7B") (pin "3") (pinfunction "VDD_3") (pintype "power_in"))
      (node (ref "X1") (pin "1") (pinfunction "1_1") (pintype "passive"))
    )
    (net (code "3") (name "+12V") (class "Default")
      (node (ref "C10") (pin "1") (pinfunction "1_1") (pintype "passive"))
      (node (ref "C6") (pin "1") (pinfunction "1_1") (pintype "passive"))
      (node (ref "C7") (pin "1") (pinfunction "1_1") (pintype "passive"))
      (node (ref "J3") (pin "1") (pinfunction "1_1") (pintype "passive"))
      (node (ref "JP10") (pin "3") (pinfunction "3_3") (pintype "passive"))
      (node (ref "JP4") (pin "2") (pinfunction "2_2") (pintype "passive"))
      (node (ref "SJ11") (pin "P$2") (pinfunction "2_P$2") (pintype "passive"))
      (node (ref "SJ14") (pin "P$2") (pinfunction "2_P$2") (pintype "passive"))
      (node (ref "SJ2") (pin "P$2") (pinfunction "2_P$2") (pintype "passive"))
      (node (ref "SJ5") (pin "P$2") (pinfunction "2_P$2") (pintype "passive"))
      (node (ref "SJ8") (pin "P$2") (pinfunction "2_P$2") (pintype "passive"))
      (node (ref "U10") (pin "4") (pinfunction "V+_4") (pintype "power_in"))
      (node (ref "U3") (pin "6") (pinfunction "VDD_6") (pintype "power_in"))
      (node (ref "U4") (pin "6") (pinfunction "VDD_6") (pintype "power_in"))
      (node (ref "U5") (pin "6") (pinfunction "VDD_6") (pintype "power_in"))
      (node (ref "U6") (pin "6") (pinfunction "VDD_6") (pintype "power_in"))
      (node (ref "U8") (pin "1") (pinfunction "VIN_1") (pintype "bidirectional"))
      (node (ref "U8B") (pin "5") (pinfunction "IN_5") (pintype "input"))
      (node (ref "U9") (pin "4") (pinfunction "V+_4") (pintype "power_in"))
    )
    (net (code "4") (name "/AGND") (class "Default")
      (node (ref "U$1") (pin "AGND") (pinfunction "AGND_AGND") (pintype "power_in"))
    )
    (net (code "5") (name "/AVDD") (class "Default")
      (node (ref "U$1") (pin "AVDD") (pinfunction "AVDD_AVDD") (pintype "power_in"))
    )
    (net (code "6") (name "/CANH") (class "Default")
      (node (ref "J1") (pin "1") (pinfunction "1_1") (pintype "passive"))
      (node (ref "J2") (pin "1") (pinfunction "1_1") (pintype "passive"))
      (node (ref "U7") (pin "7") (pinfunction "CANH_7") (pintype "bidirectional"))
      (node (ref "U7B") (pin "7") (pinfunction "CANH_7") (pintype "bidirectional"))
    )
    (net (code "7") (name "/CANL") (class "Default")
      (node (ref "J1") (pin "2") (pinfunction "2_2") (pintype "passive"))
      (node (ref "J2") (pin "2") (pinfunction "2_2") (pintype "passive"))
      (node (ref "U7") (pin "6") (pinfunction "CANL_6") (pintype "bidirectional"))
      (node (ref "U7B") (pin "6") (pinfunction "CANL_6") (pintype "bidirectional"))
    )
    (net (code "8") (name "/GND4") (class "Default")
      (node (ref "U$1") (pin "GND4") (pinfunction "GND4_GND4") (pintype "power_in"))
    )
    (net (code "9") (name "/PWR_POS") (class "Default")
      (node (ref "J1") (pin "8") (pinfunction "8_8") (pintype "passive"))
      (node (ref "J2") (pin "8") (pinfunction "8_8") (pintype "passive"))
      (node (ref "R40") (pin "1") (pinfunction "1_1") (pintype "passive"))
    )
    (net (code "10") (name "/U5V") (class "Default")
      (node (ref "U$1") (pin "U5V") (pinfunction "U5V_U5V") (pintype "power_in"))
    )
    (net (code "11") (name "/VBAT") (class "Default")
      (node (ref "U$1") (pin "VBAT") (pinfunction "VBAT_VBAT") (pintype "power_in"))
    )
    (net (code "12") (name "/VDD") (class "Default")
      (node (ref "U$1") (pin "VDD") (pinfunction "VDD_VDD") (pintype "power_in"))
    )
    (net (code "13") (name "CANRX") (class "Default")
      (node (ref "U$1") (pin "PB8") (pinfunction "PB8_PB8") (pintype "bidirectional"))
      (node (ref "U7") (pin "4") (pinfunction "RXD_4") (pintype "output"))
      (node (ref "U7B") (pin "4") (pinfunction "RXD_4") (pintype "bidirectional"))
    )
    (net (code "14") (name "CANTX") (class "Default")
      (node (ref "U$1") (pin "PB9") (pinfunction "PB9_PB9") (pintype "bidirectional"))
      (node (ref "U7") (pin "1") (pinfunction "TXD_1") (pintype "input"))
      (node (ref "U7B") (pin "1") (pinfunction "TXD_1") (pintype "bidirectional"))
    )
    (net (code "15") (name "E_CS") (class "Default")
      (node (ref "JP9") (pin "4") (pinfunction "4_4") (pintype "passive"))
      (node (ref "R23") (pin "2") (pinfunction "2_2") (pintype "passive"))
      (node (ref "U$1") (pin "PC10") (pinfunction "PC10_PC10") (pintype "bidirectional"))
    )
    (net (code "16") (name "E_LAT") (class "Default")
      (node (ref "JP10") (pin "1") (pinfunction "1_1") (pintype "passive"))
      (node (ref "R22") (pin "2") (pinfunction "2_2") (pintype "passive"))
      (node (ref "U$1") (pin "PC11") (pinfunction "PC11_PC11") (pintype "bidirectional"))
    )
    (net (code "17") (name "GND") (class "Default")
      (node (ref "C1") (pin "2") (pinfunction "2_2") (pintype "passive"))
      (node (ref "C10") (pin "2") (pinfunction "2_2") (pintype "passive"))
      (node (ref "C11") (pin "2") (pinfunction "2_2") (pintype "passive"))
      (node (ref "C2") (pin "-") (pinfunction "-_-") (pintype "passive"))
      (node (ref "C3") (pin "2") (pinfunction "2_2") (pintype "passive"))
      (node (ref "C4") (pin "2") (pinfunction "2_2") (pintype "passive"))
      (node (ref "C5") (pin "2") (pinfunction "2_2") (pintype "passive"))
      (node (ref "C6") (pin "2") (pinfunction "2_2") (pintype "passive"))
      (node (ref "C7") (pin "2") (pinfunction "2_2") (pintype "passive"))
      (node (ref "C8") (pin "2") (pinfunction "2_2") (pintype "passive"))
      (node (ref "C9") (pin "2") (pinfunction "2_2") (pintype "passive"))
      (node (ref "D1") (pin "A") (pinfunction "A_A") (pintype "passive"))
      (node (ref "J1") (pin "3") (pinfunction "3_3") (pintype "passive"))
      (node (ref "J1") (pin "6") (pinfunction "6_6") (pintype "passive"))
      (node (ref "J1") (pin "7") (pinfunction "7_7") (pintype "passive"))
      (node (ref "J2") (pin "3") (pinfunction "3_3") (pintype "passive"))
      (node (ref "J2") (pin "6") (pinfunction "6_6") (pintype "passive"))
      (node (ref "J2") (pin "7") (pinfunction "7_7") (pintype "passive"))
      (node (ref "J3") (pin "2") (pinfunction "2_2") (pintype "passive"))
      (node (ref "J3") (pin "3") (pinfunction "3_3") (pintype "passive"))
      (node (ref "JP10") (pin "4") (pinfunction "4_4") (pintype "passive"))
      (node (ref "JP11") (pin "5") (pinfunction "5_5") (pintype "passive"))
      (node (ref "JP11") (pin "6") (pinfunction "6_6") (pintype "passive"))
      (node (ref "JP12") (pin "5") (pinfunction "5_5") (pintype "passive"))
      (node (ref "JP12") (pin "6") (pinfunction "6_6") (pintype "passive"))
      (node (ref "JP16") (pin "5") (pinfunction "5_5") (pintype "passive"))
      (node (ref "JP16") (pin "6") (pinfunction "6_6") (pintype "passive"))
      (node (ref "JP7") (pin "5") (pinfunction "5_5") (pintype "passive"))
      (node (ref "JP7") (pin "6") (pinfunction "6_6") (pintype "passive"))
      (node (ref "JP8") (pin "4") (pinfunction "4_4") (pintype "passive"))
      (node (ref "PORTA") (pin "5") (pinfunction "5_5") (pintype "passive"))
      (node (ref "PORTB") (pin "5") (pinfunction "5_5") (pintype "passive"))
      (node (ref "PORTC") (pin "5") (pinfunction "5_5") (pintype "passive"))
      (node (ref "Q1") (pin "2") (pinfunction "S_2") (pintype "passive"))
      (node (ref "Q10") (pin "2") (pinfunction "S_2") (pintype "passive"))
      (node (ref "Q11") (pin "2") (pinfunction "S_2") (pintype "passive"))
      (node (ref "Q12") (pin "2") (pinfunction "S_2") (pintype "passive"))
      (node (ref "Q13") (pin "2") (pinfunction "S_2") (pintype "passive"))
      (node (ref "Q14") (pin "2") (pinfunction "S_2") (pintype "passive"))
      (node (ref "Q15") (pin "2") (pinfunction "S_2") (pintype "passive"))
      (node (ref "Q16") (pin "2") (pinfunction "S_2") (pintype "passive"))
      (node (ref "Q2") (pin "2") (pinfunction "S_2") (pintype "passive"))
      (node (ref "Q3") (pin "2") (pinfunction "S_2") (pintype "passive"))
      (node (ref "Q4") (pin "2") (pinfunction "S_2") (pintype "passive"))
      (node (ref "Q5") (pin "2") (pinfunction "S_2") (pintype "passive"))
      (node (ref "Q6") (pin "2") (pinfunction "S_2") (pintype "passive"))
      (node (ref "Q7") (pin "2") (pinfunction "S_2") (pintype "passive"))
      (node (ref "Q8") (pin "2") (pinfunction "S_2") (pintype "passive"))
      (node (ref "Q9") (pin "2") (pinfunction "S_2") (pintype "passive"))
      (node (ref "R2") (pin "1") (pinfunction "1_1") (pintype "passive"))
      (node (ref "R61") (pin "2") (pinfunction "2_2") (pintype "passive"))
      (node (ref "SJ12") (pin "P$2") (pinfunction "2_P$2") (pintype "passive"))
      (node (ref "SJ3") (pin "2") (pinfunction "2_2") (pintype "passive"))
      (node (ref "SJ6") (pin "P$2") (pinfunction "2_P$2") (pintype "passive"))
      (node (ref "SJ9") (pin "2") (pinfunction "2_2") (pintype "passive"))
      (node (ref "U$1") (pin "GND3") (pinfunction "GND3_GND3") (pintype "power_in"))
      (node (ref "U$1") (pin "GND5") (pinfunction "GND5_GND5") (pintype "power_in"))
      (node (ref "U$1") (pin "GND6") (pinfunction "GND6_GND6") (pintype "power_in"))
      (node (ref "U$1") (pin "GND7") (pinfunction "GND7_GND7") (pintype "power_in"))
      (node (ref "U$1") (pin "GND8") (pinfunction "GND8_GND8") (pintype "power_in"))
      (node (ref "U1") (pin "6") (pinfunction "INH_6") (pintype "input"))
      (node (ref "U1") (pin "8") (pinfunction "GND_8") (pintype "power_in"))
      (node (ref "U10") (pin "11") (pinfunction "V-_11") (pintype "power_in"))
      (node (ref "U11") (pin "13") (pinfunction "G_13") (pintype "input"))
      (node (ref "U11") (pin "8") (pinfunction "GND_8") (pintype "power_in"))
      (node (ref "U13") (pin "13") (pinfunction "G_13") (pintype "input"))
      (node (ref "U13") (pin "8") (pinfunction "GND_8") (pintype "power_in"))
      (node (ref "U2") (pin "6") (pinfunction "INH_6") (pintype "input"))
      (node (ref "U2") (pin "8") (pinfunction "GND_8") (pintype "power_in"))
      (node (ref "U3") (pin "3") (pinfunction "VSS_3") (pintype "power_in"))
      (node (ref "U4") (pin "3") (pinfunction "VSS_3") (pintype "power_in"))
      (node (ref "U5") (pin "3") (pinfunction "VSS_3") (pintype "power_in"))
      (node (ref "U6") (pin "3") (pinfunction "VSS_3") (pintype "power_in"))
      (node (ref "U7") (pin "2") (pinfunction "GND_2") (pintype "power_in"))
      (node (ref "U7B") (pin "2") (pinfunction "VSS_2") (pintype "power_in"))
      (node (ref "U8") (pin "4") (pinfunction "SD_4") (pintype "bidirectional"))
      (node (ref "U8") (pin "5") (pinfunction "GND1_5") (pintype "power_in"))
      (node (ref "U8") (pin "6") (pinfunction "GND2_6") (pintype "power_in"))
      (node (ref "U8") (pin "7") (pinfunction "GND3_7") (pintype "power_in"))
      (node (ref "U8") (pin "8") (pinfunction "GND4_8") (pintype "power_in"))
      (node (ref "U8B") (pin "2") (pinfunction "GNDSIG_2") (pintype "input"))
      (node (ref "U8B") (pin "3") (pinfunction "~{ON/OFF}_3") (pintype "input"))
      (node (ref "U8B") (pin "4") (pinfunction "GND_4") (pintype "power_in"))
      (node (ref "U9") (pin "11") (pinfunction "V-_11") (pintype "power_in"))
      (node (ref "X1") (pin "2") (pinfunction "2_2") (pintype "passive"))
    )
    (net (code "18") (name "I2CSCL") (class "Default")
      (node (ref "JP8") (pin "2") (pinfunction "2_2") (pintype "passive"))
      (node (ref "R63") (pin "2") (pinfunction "2_2") (pintype "passive"))
      (node (ref "U$1") (pin "PB6") (pinfunction "PB6_PB6") (pintype "bidirectional"))
    )
    (net (code "19") (name "I2CSDA") (class "Default")
      (node (ref "JP8") (pin "1") (pinfunction "1_1") (pintype "passive"))
      (node (ref "R62") (pin "2") (pinfunction "2_2") (pintype "passive"))
      (node (ref "U$1") (pin "PB7") (pinfunction "PB7_PB7") (pintype "bidirectional"))
    )
    (net (code "20") (name "ILAT") (class "Default")
      (node (ref "U$1") (pin "PA6") (pinfunction "PA6_PA6") (pintype "bidirectional"))
      (node (ref "U1") (pin "15") (pinfunction "SH/~{LD}_15") (pintype "input"))
      (node (ref "U2") (pin "15") (pinfunction "SH/~{LD}_15") (pintype "input"))
    )
    (net (code "21") (name "MISO") (class "Default")
      (node (ref "JP9") (pin "1") (pinfunction "1_1") (pintype "passive"))
      (node (ref "U$1") (pin "PB4") (pinfunction "PB4_PB4") (pintype "bidirectional"))
    )
    (net (code "22") (name "MISO2") (class "Default")
      (node (ref "SJ13") (pin "P$2") (pinfunction "2_P$2") (pintype "passive"))
      (node (ref "U$1") (pin "PC2") (pinfunction "PC2_PC2") (pintype "bidirectional"))
      (node (ref "U2") (pin "13") (pinfunction "QH_13") (pintype "output"))
    )
    (net (code "23") (name "MOSI") (class "Default")
      (node (ref "R20") (pin "1") (pinfunction "1_1") (pintype "passive"))
      (node (ref "SJ15") (pin "1") (pinfunction "1_1") (pintype "passive"))
      (node (ref "SJ17") (pin "P$2") (pinfunction "2_P$2") (pintype "passive"))
      (node (ref "U$1") (pin "PB5") (pinfunction "PB5_PB5") (pintype "bidirectional"))
      (node (ref "U11") (pin "14") (pinfunction "SER_14") (pintype "input"))
    )
    (net (code "24") (name "Net-(D2-PadA)") (class "Default")
      (node (ref "D2") (pin "A") (pinfunction "A_A") (pintype "passive"))
      (node (ref "JP4") (pin "4") (pinfunction "4_4") (pintype "passive"))
    )
    (net (code "25") (name "Net-(D2-PadC)") (class "Default")
      (node (ref "D2") (pin "C") (pinfunction "C_C") (pintype "passive"))
      (node (ref "JP4") (pin "1") (pinfunction "1_1") (pintype "passive"))
    )
    (net (code "26") (name "Net-(J1-Pad4)") (class "Default")
      (node (ref "J1") (pin "4") (pinfunction "4_4") (pintype "passive"))
      (node (ref "J2") (pin "4") (pinfunction "4_4") (pintype "passive"))
    )
    (net (code "27") (name "Net-(J1-Pad5)") (class "Default")
      (node (ref "J1") (pin "5") (pinfunction "5_5") (pintype "passive"))
      (node (ref "J2") (pin "5") (pinfunction "5_5") (pintype "passive"))
    )
    (net (code "28") (name "Net-(JP2-Pad1)") (class "Default")
      (node (ref "JP2") (pin "1") (pinfunction "1_1") (pintype "passive"))
      (node (ref "PORTB") (pin "1") (pinfunction "1_1") (pintype "passive"))
      (node (ref "R35") (pin "2") (pinfunction "2_2") (pintype "passive"))
      (node (ref "R45") (pin "2") (pinfunction "2_2") (pintype "passive"))
      (node (ref "RN1") (pin "1") (pinfunction "1_1") (pintype "passive"))
      (node (ref "RN2") (pin "9") (pinfunction "9_9") (pintype "passive"))
    )
    (net (code "29") (name "Net-(JP3-Pad1)") (class "Default")
      (node (ref "JP3") (pin "1") (pinfunction "1_1") (pintype "passive"))
      (node (ref "PORTA") (pin "1") (pinfunction "1_1") (pintype "passive"))
      (node (ref "R44") (pin "2") (pinfunction "2_2") (pintype "passive"))
      (node (ref "R53") (pin "2") (pinfunction "2_2") (pintype "passive"))
      (node (ref "RN3") (pin "1") (pinfunction "1_1") (pintype "passive"))
      (node (ref "RN4") (pin "9") (pinfunction "9_9") (pintype "passive"))
    )
    (net (code "30") (name "Net-(JP4-Pad3)") (class "Default")
      (node (ref "JP4") (pin "3") (pinfunction "3_3") (pintype "passive"))
      (node (ref "R40") (pin "2") (pinfunction "2_2") (pintype "passive"))
    )
    (net (code "31") (name "Net-(Q1-D)") (class "Default")
      (node (ref "JP1") (pin "1") (pinfunction "1_1") (pintype "passive"))
      (node (ref "Q1") (pin "3") (pinfunction "D_3") (pintype "passive"))
      (node (ref "U12") (pin "18") (pinfunction "O1_18") (pintype "open_collector"))
    )
    (net (code "32") (name "Net-(Q1-G)") (class "Default")
      (node (ref "Q1") (pin "1") (pinfunction "G_1") (pintype "passive"))
      (node (ref "R3") (pin "2") (pinfunction "2_2") (pintype "passive"))
    )
    (net (code "33") (name "Net-(Q2-D)") (class "Default")
      (node (ref "JP1") (pin "2") (pinfunction "2_2") (pintype "passive"))
      (node (ref "Q2") (pin "3") (pinfunction "D_3") (pintype "passive"))
      (node (ref "U12") (pin "17") (pinfunction "O2_17") (pintype "open_collector"))
    )
    (net (code "34") (name "Net-(Q2-G)") (class "Default")
      (node (ref "Q2") (pin "1") (pinfunction "G_1") (pintype "passive"))
      (node (ref "R4") (pin "2") (pinfunction "2_2") (pintype "passive"))
    )
    (net (code "35") (name "Net-(Q3-D)") (class "Default")
      (node (ref "JP1") (pin "3") (pinfunction "3_3") (pintype "passive"))
      (node (ref "Q3") (pin "3") (pinfunction "D_3") (pintype "passive"))
      (node (ref "U12") (pin "16") (pinfunction "O3_16") (pintype "open_collector"))
    )
    (net (code "36") (name "Net-(Q3-G)") (class "Default")
      (node (ref "Q3") (pin "1") (pinfunction "G_1") (pintype "passive"))
      (node (ref "R5") (pin "2") (pinfunction "2_2") (pintype "passive"))
    )
    (net (code "37") (name "Net-(Q4-D)") (class "Default")
      (node (ref "JP1") (pin "4") (pinfunction "4_4") (pintype "passive"))
      (node (ref "Q4") (pin "3") (pinfunction "D_3") (pintype "passive"))
      (node (ref "U12") (pin "15") (pinfunction "O4_15") (pintype "open_collector"))
    )
    (net (code "38") (name "Net-(Q4-G)") (class "Default")
      (node (ref "Q4") (pin "1") (pinfunction "G_1") (pintype "passive"))
      (node (ref "R6") (pin "2") (pinfunction "2_2") (pintype "passive"))
    )
    (net (code "39") (name "Net-(Q5-D)") (class "Default")
      (node (ref "JP1") (pin "5") (pinfunction "5_5") (pintype "passive"))
      (node (ref "Q5") (pin "3") (pinfunction "D_3") (pintype "passive"))
      (node (ref "U12") (pin "14") (pinfunction "O5_14") (pintype "open_collector"))
    )
    (net (code "40") (name "Net-(Q5-G)") (class "Default")
      (node (ref "Q5") (pin "1") (pinfunction "G_1") (pintype "passive"))
      (node (ref "R7") (pin "2") (pinfunction "2_2") (pintype "passive"))
    )
    (net (code "41") (name "Net-(Q6-D)") (class "Default")
      (node (ref "JP1") (pin "6") (pinfunction "6_6") (pintype "passive"))
      (node (ref "Q6") (pin "3") (pinfunction "D_3") (pintype "passive"))
      (node (ref "U12") (pin "13") (pinfunction "O6_13") (pintype "open_collector"))
    )
    (net (code "42") (name "Net-(Q6-G)") (class "Default")
      (node (ref "Q6") (pin "1") (pinfunction "G_1") (pintype "passive"))
      (node (ref "R8") (pin "2") (pinfunction "2_2") (pintype "passive"))
    )
    (net (code "43") (name "Net-(Q7-D)") (class "Default")
      (node (ref "JP1") (pin "7") (pinfunction "7_7") (pintype "passive"))
      (node (ref "Q7") (pin "3") (pinfunction "D_3") (pintype "passive"))
      (node (ref "U12") (pin "12") (pinfunction "O7_12") (pintype "open_collector"))
    )
    (net (code "44") (name "Net-(Q7-G)") (class "Default")
      (node (ref "Q7") (pin "1") (pinfunction "G_1") (pintype "passive"))
      (node (ref "R9") (pin "2") (pinfunction "2_2") (pintype "passive"))
    )
    (net (code "45") (name "Net-(Q8-D)") (class "Default")
      (node (ref "JP1") (pin "8") (pinfunction "8_8") (pintype "passive"))
      (node (ref "Q8") (pin "3") (pinfunction "D_3") (pintype "passive"))
      (node (ref "U12") (pin "11") (pinfunction "O8_11") (pintype "open_collector"))
    )
    (net (code "46") (name "Net-(Q8-G)") (class "Default")
      (node (ref "Q8") (pin "1") (pinfunction "G_1") (pintype "passive"))
      (node (ref "R10") (pin "2") (pinfunction "2_2") (pintype "passive"))
    )
    (net (code "47") (name "Net-(Q9-D)") (class "Default")
      (node (ref "JP6") (pin "1") (pinfunction "1_1") (pintype "passive"))
      (node (ref "Q9") (pin "3") (pinfunction "D_3") (pintype "passive"))
      (node (ref "U14") (pin "18") (pinfunction "O1_18") (pintype "open_collector"))
    )
    (net (code "48") (name "Net-(Q9-G)") (class "Default")
      (node (ref "Q9") (pin "1") (pinfunction "G_1") (pintype "passive"))
      (node (ref "R11") (pin "2") (pinfunction "2_2") (pintype "passive"))
    )
    (net (code "49") (name "Net-(Q10-D)") (class "Default")
      (node (ref "JP6") (pin "2") (pinfunction "2_2") (pintype "passive"))
      (node (ref "Q10") (pin "3") (pinfunction "D_3") (pintype "passive"))
      (node (ref "U14") (pin "17") (pinfunction "O2_17") (pintype "open_collector"))
    )
    (net (code "50") (name "Net-(Q10-G)") (class "Default")
      (node (ref "Q10") (pin "1") (pinfunction "G_1") (pintype "passive"))
      (node (ref "R12") (pin "2") (pinfunction "2_2") (pintype "passive"))
    )
    (net (code "51") (name "Net-(Q11-D)") (class "Default")
      (node (ref "JP6") (pin "3") (pinfunction "3_3") (pintype "passive"))
      (node (ref "Q11") (pin "3") (pinfunction "D_3") (pintype "passive"))
      (node (ref "U14") (pin "16") (pinfunction "O3_16") (pintype "open_collector"))
    )
    (net (code "52") (name "Net-(Q11-G)") (class "Default")
      (node (ref "Q11") (pin "1") (pinfunction "G_1") (pintype "passive"))
      (node (ref "R13") (pin "2") (pinfunction "2_2") (pintype "passive"))
    )
    (net (code "53") (name "Net-(Q12-D)") (class "Default")
      (node (ref "JP6") (pin "4") (pinfunction "4_4") (pintype "passive"))
      (node (ref "Q12") (pin "3") (pinfunction "D_3") (pintype "passive"))
      (node (ref "U14") (pin "15") (pinfunction "O4_15") (pintype "open_collector"))
    )
    (net (code "54") (name "Net-(Q12-G)") (class "Default")
      (node (ref "Q12") (pin "1") (pinfunction "G_1") (pintype "passive"))
      (node (ref "R14") (pin "2") (pinfunction "2_2") (pintype "passive"))
    )
    (net (code "55") (name "Net-(Q13-D)") (class "Default")
      (node (ref "JP6") (pin "5") (pinfunction "5_5") (pintype "passive"))
      (node (ref "Q13") (pin "3") (pinfunction "D_3") (pintype "passive"))
      (node (ref "U14") (pin "14") (pinfunction "O5_14") (pintype "open_collector"))
    )
    (net (code "56") (name "Net-(Q13-G)") (class "Default")
      (node (ref "Q13") (pin "1") (pinfunction "G_1") (pintype "passive"))
      (node (ref "R15") (pin "2") (pinfunction "2_2") (pintype "passive"))
    )
    (net (code "57") (name "Net-(Q14-D)") (class "Default")
      (node (ref "JP6") (pin "6") (pinfunction "6_6") (pintype "passive"))
      (node (ref "Q14") (pin "3") (pinfunction "D_3") (pintype "passive"))
      (node (ref "U14") (pin "13") (pinfunction "O6_13") (pintype "open_collector"))
    )
    (net (code "58") (name "Net-(Q14-G)") (class "Default")
      (node (ref "Q14") (pin "1") (pinfunction "G_1") (pintype "passive"))
      (node (ref "R16") (pin "2") (pinfunction "2_2") (pintype "passive"))
    )
    (net (code "59") (name "Net-(Q15-D)") (class "Default")
      (node (ref "JP6") (pin "7") (pinfunction "7_7") (pintype "passive"))
      (node (ref "Q15") (pin "3") (pinfunction "D_3") (pintype "passive"))
      (node (ref "U14") (pin "12") (pinfunction "O7_12") (pintype "open_collector"))
    )
    (net (code "60") (name "Net-(Q15-G)") (class "Default")
      (node (ref "Q15") (pin "1") (pinfunction "G_1") (pintype "passive"))
      (node (ref "R17") (pin "2") (pinfunction "2_2") (pintype "passive"))
    )
    (net (code "61") (name "Net-(Q16-D)") (class "Default")
      (node (ref "JP6") (pin "8") (pinfunction "8_8") (pintype "passive"))
      (node (ref "Q16") (pin "3") (pinfunction "D_3") (pintype "passive"))
      (node (ref "U14") (pin "11") (pinfunction "O8_11") (pintype "open_collector"))
    )
    (net (code "62") (name "Net-(Q16-G)") (class "Default")
      (node (ref "Q16") (pin "1") (pinfunction "G_1") (pintype "passive"))
      (node (ref "R18") (pin "2") (pinfunction "2_2") (pintype "passive"))
    )
    (net (code "63") (name "Net-(RN1A-2)") (class "Default")
      (node (ref "R35") (pin "1") (pinfunction "1_1") (pintype "passive"))
      (node (ref "RN1") (pin "16") (pinfunction "2_16") (pintype "passive"))
      (node (ref "U2") (pin "14") (pinfunction "H_14") (pintype "input"))
    )
    (net (code "64") (name "Net-(RN1B-1)") (class "Default")
      (node (ref "JP2") (pin "2") (pinfunction "2_2") (pintype "passive"))
      (node (ref "PORTB") (pin "2") (pinfunction "2_2") (pintype "passive"))
      (node (ref "R34") (pin "2") (pinfunction "2_2") (pintype "passive"))
      (node (ref "R46") (pin "1") (pinfunction "1_1") (pintype "passive"))
      (node (ref "RN1") (pin "2") (pinfunction "1_2") (pintype "passive"))
      (node (ref "RN2") (pin "8") (pinfunction "8_8") (pintype "passive"))
    )
    (net (code "65") (name "Net-(RN1B-2)") (class "Default")
      (node (ref "R34") (pin "1") (pinfunction "1_1") (pintype "passive"))
      (node (ref "RN1") (pin "15") (pinfunction "2_15") (pintype "passive"))
      (node (ref "U2") (pin "12") (pinfunction "G_12") (pintype "input"))
    )
    (net (code "66") (name "Net-(RN1C-1)") (class "Default")
      (node (ref "JP2") (pin "3") (pinfunction "3_3") (pintype "passive"))
      (node (ref "PORTB") (pin "3") (pinfunction "3_3") (pintype "passive"))
      (node (ref "R33") (pin "2") (pinfunction "2_2") (pintype "passive"))
      (node (ref "R47") (pin "1") (pinfunction "1_1") (pintype "passive"))
      (node (ref "RN1") (pin "3") (pinfunction "1_3") (pintype "passive"))
      (node (ref "RN2") (pin "7") (pinfunction "7_7") (pintype "passive"))
    )
    (net (code "67") (name "Net-(RN1C-2)") (class "Default")
      (node (ref "R33") (pin "1") (pinfunction "1_1") (pintype "passive"))
      (node (ref "RN1") (pin "14") (pinfunction "2_14") (pintype "passive"))
      (node (ref "U2") (pin "11") (pinfunction "F_11") (pintype "input"))
    )
    (net (code "68") (name "Net-(RN1D-1)") (class "Default")
      (node (ref "JP2") (pin "4") (pinfunction "4_4") (pintype "passive"))
      (node (ref "PORTB") (pin "4") (pinfunction "4_4") (pintype "passive"))
      (node (ref "R32") (pin "2") (pinfunction "2_2") (pintype "passive"))
      (node (ref "R48") (pin "1") (pinfunction "1_1") (pintype "passive"))
      (node (ref "RN1") (pin "4") (pinfunction "1_4") (pintype "passive"))
      (node (ref "RN2") (pin "6") (pinfunction "6_6") (pintype "passive"))
    )
    (net (code "69") (name "Net-(RN1D-2)") (class "Default")
      (node (ref "R32") (pin "1") (pinfunction "1_1") (pintype "passive"))
      (node (ref "RN1") (pin "13") (pinfunction "2_13") (pintype "passive"))
      (node (ref "U2") (pin "10") (pinfunction "E_10") (pintype "input"))
    )
    (net (code "70") (name "Net-(RN1E-1)") (class "Default")
      (node (ref "JP2") (pin "5") (pinfunction "5_5") (pintype "passive"))
      (node (ref "PORTB") (pin "7") (pinfunction "7_7") (pintype "passive"))
      (node (ref "R31") (pin "2") (pinfunction "2_2") (pintype "passive"))
      (node (ref "R49") (pin "1") (pinfunction "1_1") (pintype "passive"))
      (node (ref "RN1") (pin "5") (pinfunction "1_5") (pintype "passive"))
      (node (ref "RN2") (pin "5") (pinfunction "5_5") (pintype "passive"))
    )
    (net (code "71") (name "Net-(RN1E-2)") (class "Default")
      (node (ref "R31") (pin "1") (pinfunction "1_1") (pintype "passive"))
      (node (ref "RN1") (pin "12") (pinfunction "2_12") (pintype "passive"))
      (node (ref "U2") (pin "5") (pinfunction "D_5") (pintype "input"))
    )
    (net (code "72") (name "Net-(RN1F-1)") (class "Default")
      (node (ref "JP2") (pin "6") (pinfunction "6_6") (pintype "passive"))
      (node (ref "PORTB") (pin "8") (pinfunction "8_8") (pintype "passive"))
      (node (ref "R30") (pin "2") (pinfunction "2_2") (pintype "passive"))
      (node (ref "R50") (pin "1") (pinfunction "1_1") (pintype "passive"))
      (node (ref "RN1") (pin "6") (pinfunction "1_6") (pintype "passive"))
      (node (ref "RN2") (pin "4") (pinfunction "4_4") (pintype "passive"))
    )
    (net (code "73") (name "Net-(RN1F-2)") (class "Default")
      (node (ref "R30") (pin "1") (pinfunction "1_1") (pintype "passive"))
      (node (ref "RN1") (pin "11") (pinfunction "2_11") (pintype "passive"))
      (node (ref "U2") (pin "4") (pinfunction "C_4") (pintype "input"))
    )
    (net (code "74") (name "Net-(RN1G-1)") (class "Default")
      (node (ref "JP2") (pin "7") (pinfunction "7_7") (pintype "passive"))
      (node (ref "PORTB") (pin "9") (pinfunction "9_9") (pintype "passive"))
      (node (ref "R29") (pin "2") (pinfunction "2_2") (pintype "passive"))
      (node (ref "R51") (pin "1") (pinfunction "1_1") (pintype "passive"))
      (node (ref "RN1") (pin "7") (pinfunction "1_7") (pintype "passive"))
      (node (ref "RN2") (pin "3") (pinfunction "3_3") (pintype "passive"))
    )
    (net (code "75") (name "Net-(RN1G-2)") (class "Default")
      (node (ref "R29") (pin "1") (pinfunction "1_1") (pintype "passive"))
      (node (ref "RN1") (pin "10") (pinfunction "2_10") (pintype "passive"))
      (node (ref "U2") (pin "3") (pinfunction "B_3") (pintype "input"))
    )
    (net (code "76") (name "Net-(RN1H-1)") (class "Default")
      (node (ref "JP2") (pin "8") (pinfunction "8_8") (pintype "passive"))
      (node (ref "PORTB") (pin "10") (pinfunction "10_10") (pintype "passive"))
      (node (ref "R28") (pin "2") (pinfunction "2_2") (pintype "passive"))
      (node (ref "R52") (pin "1") (pinfunction "1_1") (pintype "passive"))
      (node (ref "RN1") (pin "8") (pinfunction "1_8") (pintype "passive"))
      (node (ref "RN2") (pin "2") (pinfunction "2_2") (pintype "passive"))
    )
    (net (code "77") (name "Net-(RN1H-2)") (class "Default")
      (node (ref "R28") (pin "1") (pinfunction "1_1") (pintype "passive"))
      (node (ref "RN1") (pin "9") (pinfunction "2_9") (pintype "passive"))
      (node (ref "U2") (pin "2") (pinfunction "A_2") (pintype "input"))
    )
    (net (code "78") (name "Net-(RN3A-2)") (class "Default")
      (node (ref "R44") (pin "1") (pinfunction "1_1") (pintype "passive"))
      (node (ref "RN3") (pin "16") (pinfunction "2_16") (pintype "passive"))
      (node (ref "U1") (pin "14") (pinfunction "H_14") (pintype "input"))
    )
    (net (code "79") (name "Net-(RN3B-1)") (class "Default")
      (node (ref "JP3") (pin "2") (pinfunction "2_2") (pintype "passive"))
      (node (ref "PORTA") (pin "2") (pinfunction "2_2") (pintype "passive"))
      (node (ref "R43") (pin "2") (pinfunction "2_2") (pintype "passive"))
      (node (ref "R54") (pin "2") (pinfunction "2_2") (pintype "passive"))
      (node (ref "RN3") (pin "2") (pinfunction "1_2") (pintype "passive"))
      (node (ref "RN4") (pin "8") (pinfunction "8_8") (pintype "passive"))
    )
    (net (code "80") (name "Net-(RN3B-2)") (class "Default")
      (node (ref "R43") (pin "1") (pinfunction "1_1") (pintype "passive"))
      (node (ref "RN3") (pin "15") (pinfunction "2_15") (pintype "passive"))
      (node (ref "U1") (pin "12") (pinfunction "G_12") (pintype "input"))
    )
    (net (code "81") (name "Net-(RN3C-1)") (class "Default")
      (node (ref "JP3") (pin "3") (pinfunction "3_3") (pintype "passive"))
      (node (ref "PORTA") (pin "3") (pinfunction "3_3") (pintype "passive"))
      (node (ref "R42") (pin "2") (pinfunction "2_2") (pintype "passive"))
      (node (ref "R55") (pin "2") (pinfunction "2_2") (pintype "passive"))
      (node (ref "RN3") (pin "3") (pinfunction "1_3") (pintype "passive"))
      (node (ref "RN4") (pin "7") (pinfunction "7_7") (pintype "passive"))
    )
    (net (code "82") (name "Net-(RN3C-2)") (class "Default")
      (node (ref "R42") (pin "1") (pinfunction "1_1") (pintype "passive"))
      (node (ref "RN3") (pin "14") (pinfunction "2_14") (pintype "passive"))
      (node (ref "U1") (pin "11") (pinfunction "F_11") (pintype "input"))
    )
    (net (code "83") (name "Net-(RN3D-1)") (class "Default")
      (node (ref "JP3") (pin "4") (pinfunction "4_4") (pintype "passive"))
      (node (ref "PORTA") (pin "4") (pinfunction "4_4") (pintype "passive"))
      (node (ref "R41") (pin "2") (pinfunction "2_2") (pintype "passive"))
      (node (ref "R56") (pin "2") (pinfunction "2_2") (pintype "passive"))
      (node (ref "RN3") (pin "4") (pinfunction "1_4") (pintype "passive"))
      (node (ref "RN4") (pin "6") (pinfunction "6_6") (pintype "passive"))
    )
    (net (code "84") (name "Net-(RN3D-2)") (class "Default")
      (node (ref "R41") (pin "1") (pinfunction "1_1") (pintype "passive"))
      (node (ref "RN3") (pin "13") (pinfunction "2_13") (pintype "passive"))
      (node (ref "U1") (pin "10") (pinfunction "E_10") (pintype "input"))
    )
    (net (code "85") (name "Net-(RN3E-1)") (class "Default")
      (node (ref "JP3") (pin "5") (pinfunction "5_5") (pintype "passive"))
      (node (ref "PORTA") (pin "7") (pinfunction "7_7") (pintype "passive"))
      (node (ref "R39") (pin "2") (pinfunction "2_2") (pintype "passive"))
      (node (ref "R57") (pin "2") (pinfunction "2_2") (pintype "passive"))
      (node (ref "RN3") (pin "5") (pinfunction "1_5") (pintype "passive"))
      (node (ref "RN4") (pin "5") (pinfunction "5_5") (pintype "passive"))
    )
    (net (code "86") (name "Net-(RN3E-2)") (class "Default")
      (node (ref "R39") (pin "1") (pinfunction "1_1") (pintype "passive"))
      (node (ref "RN3") (pin "12") (pinfunction "2_12") (pintype "passive"))
      (node (ref "U1") (pin "5") (pinfunction "D_5") (pintype "input"))
    )
    (net (code "87") (name "Net-(RN3F-1)") (class "Default")
      (node (ref "JP3") (pin "6") (pinfunction "6_6") (pintype "passive"))
      (node (ref "PORTA") (pin "8") (pinfunction "8_8") (pintype "passive"))
      (node (ref "R38") (pin "2") (pinfunction "2_2") (pintype "passive"))
      (node (ref "R58") (pin "2") (pinfunction "2_2") (pintype "passive"))
      (node (ref "RN3") (pin "6") (pinfunction "1_6") (pintype "passive"))
      (node (ref "RN4") (pin "4") (pinfunction "4_4") (pintype "passive"))
    )
    (net (code "88") (name "Net-(RN3F-2)") (class "Default")
      (node (ref "R38") (pin "1") (pinfunction "1_1") (pintype "passive"))
      (node (ref "RN3") (pin "11") (pinfunction "2_11") (pintype "passive"))
      (node (ref "U1") (pin "4") (pinfunction "C_4") (pintype "input"))
    )
    (net (code "89") (name "Net-(RN3G-1)") (class "Default")
      (node (ref "JP3") (pin "7") (pinfunction "7_7") (pintype "passive"))
      (node (ref "PORTA") (pin "9") (pinfunction "9_9") (pintype "passive"))
      (node (ref "R37") (pin "2") (pinfunction "2_2") (pintype "passive"))
      (node (ref "R59") (pin "2") (pinfunction "2_2") (pintype "passive"))
      (node (ref "RN3") (pin "7") (pinfunction "1_7") (pintype "passive"))
      (node (ref "RN4") (pin "3") (pinfunction "3_3") (pintype "passive"))
    )
    (net (code "90") (name "Net-(RN3G-2)") (class "Default")
      (node (ref "R37") (pin "1") (pinfunction "1_1") (pintype "passive"))
      (node (ref "RN3") (pin "10") (pinfunction "2_10") (pintype "passive"))
      (node (ref "U1") (pin "3") (pinfunction "B_3") (pintype "input"))
    )
    (net (code "91") (name "Net-(RN3H-1)") (class "Default")
      (node (ref "JP3") (pin "8") (pinfunction "8_8") (pintype "passive"))
      (node (ref "PORTA") (pin "10") (pinfunction "10_10") (pintype "passive"))
      (node (ref "R36") (pin "2") (pinfunction "2_2") (pintype "passive"))
      (node (ref "R60") (pin "2") (pinfunction "2_2") (pintype "passive"))
      (node (ref "RN3") (pin "8") (pinfunction "1_8") (pintype "passive"))
      (node (ref "RN4") (pin "2") (pinfunction "2_2") (pintype "passive"))
    )
    (net (code "92") (name "Net-(RN3H-2)") (class "Default")
      (node (ref "R36") (pin "1") (pinfunction "1_1") (pintype "passive"))
      (node (ref "RN3") (pin "9") (pinfunction "2_9") (pintype "passive"))
      (node (ref "U1") (pin "2") (pinfunction "A_2") (pintype "input"))
    )
    (net (code "93") (name "Net-(SJ1-1)") (class "Default")
      (node (ref "SJ1") (pin "P$1") (pinfunction "1_P$1") (pintype "passive"))
      (node (ref "SJ2") (pin "P$1") (pinfunction "1_P$1") (pintype "passive"))
      (node (ref "SJ3") (pin "1") (pinfunction "1_1") (pintype "passive"))
      (node (ref "U12") (pin "9") (pinfunction "GND_9") (pintype "power_in"))
    )
    (net (code "94") (name "Net-(SJ4-1)") (class "Default")
      (node (ref "SJ4") (pin "P$1") (pinfunction "1_P$1") (pintype "passive"))
      (node (ref "SJ5") (pin "P$1") (pinfunction "1_P$1") (pintype "passive"))
      (node (ref "SJ6") (pin "P$1") (pinfunction "1_P$1") (pintype "passive"))
      (node (ref "U12") (pin "10") (pinfunction "CD+_10") (pintype "passive"))
    )
    (net (code "95") (name "Net-(SJ7-1)") (class "Default")
      (node (ref "SJ7") (pin "P$1") (pinfunction "1_P$1") (pintype "passive"))
      (node (ref "SJ8") (pin "P$1") (pinfunction "1_P$1") (pintype "passive"))
      (node (ref "SJ9") (pin "1") (pinfunction "1_1") (pintype "passive"))
      (node (ref "U14") (pin "9") (pinfunction "GND_9") (pintype "power_in"))
    )
    (net (code "96") (name "Net-(SJ10-1)") (class "Default")
      (node (ref "SJ10") (pin "P$1") (pinfunction "1_P$1") (pintype "passive"))
      (node (ref "SJ11") (pin "P$1") (pinfunction "1_P$1") (pintype "passive"))
      (node (ref "SJ12") (pin "P$1") (pinfunction "1_P$1") (pintype "passive"))
      (node (ref "U14") (pin "10") (pinfunction "CD+_10") (pintype "passive"))
    )
    (net (code "97") (name "Net-(SJ13-1)") (class "Default")
      (node (ref "SJ13") (pin "P$1") (pinfunction "1_P$1") (pintype "passive"))
      (node (ref "U$1") (pin "PB14") (pinfunction "PB14_PB14") (pintype "bidirectional"))
    )
    (net (code "98") (name "Net-(SJ14-1)") (class "Default")
      (node (ref "SJ14") (pin "P$1") (pinfunction "1_P$1") (pintype "passive"))
      (node (ref "U$1") (pin "VIN2") (pinfunction "VIN2_VIN2") (pintype "power_in"))
    )
    (net (code "99") (name "Net-(SJ16-2)") (class "Default")
      (node (ref "JP9") (pin "2") (pinfunction "2_2") (pintype "passive"))
      (node (ref "SJ15") (pin "2") (pinfunction "2_2") (pintype "passive"))
      (node (ref "SJ16") (pin "P$2") (pinfunction "2_P$2") (pintype "passive"))
    )
    (net (code "100") (name "Net-(SJ18-2)") (class "Default")
      (node (ref "SJ18") (pin "P$2") (pinfunction "2_P$2") (pintype "passive"))
      (node (ref "U7") (pin "5") (pinfunction "VREF_5") (pintype "output"))
      (node (ref "U7B") (pin "5") (pinfunction "VREF_5") (pintype "bidirectional"))
    )
    (net (code "101") (name "Net-(U3A-O)") (class "Default")
      (node (ref "JP5") (pin "1") (pinfunction "1_1") (pintype "passive"))
      (node (ref "PORTC") (pin "1") (pinfunction "1_1") (pintype "passive"))
      (node (ref "U3") (pin "7") (pinfunction "O_7") (pintype "output"))
      (node (ref "U9") (pin "7") (pinfunction "OUT_7") (pintype "output"))
    )
    (net (code "102") (name "Net-(U3B-O)") (class "Default")
      (node (ref "JP5") (pin "2") (pinfunction "2_2") (pintype "passive"))
      (node (ref "PORTC") (pin "2") (pinfunction "2_2") (pintype "passive"))
      (node (ref "U3") (pin "5") (pinfunction "O_5") (pintype "output"))
      (node (ref "U9") (pin "8") (pinfunction "OUT_8") (pintype "output"))
    )
    (net (code "103") (name "Net-(U4A-O)") (class "Default")
      (node (ref "JP5") (pin "4") (pinfunction "4_4") (pintype "passive"))
      (node (ref "PORTC") (pin "4") (pinfunction "4_4") (pintype "passive"))
      (node (ref "U4") (pin "7") (pinfunction "O_7") (pintype "output"))
      (node (ref "U9") (pin "14") (pinfunction "OUT_14") (pintype "output"))
    )
    (net (code "104") (name "Net-(U4B-O)") (class "Default")
      (node (ref "JP5") (pin "3") (pinfunction "3_3") (pintype "passive"))
      (node (ref "PORTC") (pin "3") (pinfunction "3_3") (pintype "passive"))
      (node (ref "U4") (pin "5") (pinfunction "O_5") (pintype "output"))
      (node (ref "U9") (pin "1") (pinfunction "OUT_1") (pintype "output"))
    )
    (net (code "105") (name "Net-(U7-RS)") (class "Default")
      (node (ref "R61") (pin "1") (pinfunction "1_1") (pintype "passive"))
      (node (ref "U7") (pin "8") (pinfunction "RS_8") (pintype "input"))
      (node (ref "U7B") (pin "8") (pinfunction "RS_8") (pintype "bidirectional"))
    )
    (net (code "106") (name "Net-(U8-VOUT)") (class "Default")
      (node (ref "D1") (pin "C") (pinfunction "C_C") (pintype "passive"))
      (node (ref "L1") (pin "2") (pinfunction "2_2") (pintype "passive"))
      (node (ref "U8") (pin "2") (pinfunction "VOUT_2") (pintype "bidirectional"))
      (node (ref "U8B") (pin "7") (pinfunction "OUT_7") (pintype "passive"))
    )
    (net (code "107") (name "Net-(U10A--IN)") (class "Default")
      (node (ref "R1") (pin "1") (pinfunction "1_1") (pintype "passive"))
      (node (ref "R2") (pin "2") (pinfunction "2_2") (pintype "passive"))
      (node (ref "U10") (pin "13") (pinfunction "-IN_13") (pintype "input"))
      (node (ref "U10") (pin "2") (pinfunction "-IN_2") (pintype "input"))
      (node (ref "U10") (pin "6") (pinfunction "-IN_6") (pintype "input"))
      (node (ref "U10") (pin "9") (pinfunction "-IN_9") (pintype "input"))
      (node (ref "U9") (pin "13") (pinfunction "-IN_13") (pintype "input"))
      (node (ref "U9") (pin "2") (pinfunction "-IN_2") (pintype "input"))
      (node (ref "U9") (pin "6") (pinfunction "-IN_6") (pintype "input"))
      (node (ref "U9") (pin "9") (pinfunction "-IN_9") (pintype "input"))
    )
    (net (code "108") (name "Net-(U10A-OUT)") (class "Default")
      (node (ref "JP5") (pin "7") (pinfunction "7_7") (pintype "passive"))
      (node (ref "PORTC") (pin "9") (pinfunction "9_9") (pintype "passive"))
      (node (ref "U10") (pin "1") (pinfunction "OUT_1") (pintype "output"))
      (node (ref "U6") (pin "5") (pinfunction "O_5") (pintype "output"))
    )
    (net (code "109") (name "Net-(U10B-OUT)") (class "Default")
      (node (ref "JP5") (pin "5") (pinfunction "5_5") (pintype "passive"))
      (node (ref "PORTC") (pin "7") (pinfunction "7_7") (pintype "passive"))
      (node (ref "U10") (pin "7") (pinfunction "OUT_7") (pintype "output"))
      (node (ref "U5") (pin "7") (pinfunction "O_7") (pintype "output"))
    )
    (net (code "110") (name "Net-(U10C-OUT)") (class "Default")
      (node (ref "JP5") (pin "6") (pinfunction "6_6") (pintype "passive"))
      (node (ref "PORTC") (pin "8") (pinfunction "8_8") (pintype "passive"))
      (node (ref "U10") (pin "8") (pinfunction "OUT_8") (pintype "output"))
      (node (ref "U5") (pin "5") (pinfunction "O_5") (pintype "output"))
    )
    (net (code "111") (name "Net-(U10D-OUT)") (class "Default")
      (node (ref "JP5") (pin "8") (pinfunction "8_8") (pintype "passive"))
      (node (ref "PORTC") (pin "10") (pinfunction "10_10") (pintype "passive"))
      (node (ref "U10") (pin "14") (pinfunction "OUT_14") (pintype "output"))
      (node (ref "U6") (pin "7") (pinfunction "O_7") (pintype "output"))
    )
    (net (code "112") (name "Net-(U11A-QA)") (class "Default")
      (node (ref "R3") (pin "1") (pinfunction "1_1") (pintype "passive"))
      (node (ref "U11") (pin "15") (pinfunction "QA_15") (pintype "tri_state"))
      (node (ref "U12") (pin "1") (pinfunction "I1_1") (pintype "input"))
    )
    (net (code "113") (name "Net-(U11A-QB)") (class "Default")
      (node (ref "R4") (pin "1") (pinfunction "1_1") (pintype "passive"))
      (node (ref "U11") (pin "1") (pinfunction "QB_1") (pintype "tri_state"))
      (node (ref "U12") (pin "2") (pinfunction "I2_2") (pintype "input"))
    )
    (net (code "114") (name "Net-(U11A-QC)") (class "Default")
      (node (ref "R5") (pin "1") (pinfunction "1_1") (pintype "passive"))
      (node (ref "U11") (pin "2") (pinfunction "QC_2") (pintype "tri_state"))
      (node (ref "U12") (pin "3") (pinfunction "I3_3") (pintype "input"))
    )
    (net (code "115") (name "Net-(U11A-QD)") (class "Default")
      (node (ref "R6") (pin "1") (pinfunction "1_1") (pintype "passive"))
      (node (ref "U11") (pin "3") (pinfunction "QD_3") (pintype "tri_state"))
      (node (ref "U12") (pin "4") (pinfunction "I4_4") (pintype "input"))
    )
    (net (code "116") (name "Net-(U11A-QE)") (class "Default")
      (node (ref "R7") (pin "1") (pinfunction "1_1") (pintype "passive"))
      (node (ref "U11") (pin "4") (pinfunction "QE_4") (pintype "tri_state"))
      (node (ref "U12") (pin "5") (pinfunction "I5_5") (pintype "input"))
    )
    (net (code "117") (name "Net-(U11A-QF)") (class "Default")
      (node (ref "R8") (pin "1") (pinfunction "1_1") (pintype "passive"))
      (node (ref "U11") (pin "5") (pinfunction "QF_5") (pintype "tri_state"))
      (node (ref "U12") (pin "6") (pinfunction "I6_6") (pintype "input"))
    )
    (net (code "118") (name "Net-(U11A-QG)") (class "Default")
      (node (ref "R9") (pin "1") (pinfunction "1_1") (pintype "passive"))
      (node (ref "U11") (pin "6") (pinfunction "QG_6") (pintype "tri_state"))
      (node (ref "U12") (pin "7") (pinfunction "I7_7") (pintype "input"))
    )
    (net (code "119") (name "Net-(U11A-QH)") (class "Default")
      (node (ref "R10") (pin "1") (pinfunction "1_1") (pintype "passive"))
      (node (ref "U11") (pin "7") (pinfunction "QH_7") (pintype "tri_state"))
      (node (ref "U12") (pin "8") (pinfunction "I8_8") (pintype "input"))
    )
    (net (code "120") (name "Net-(U13A-QA)") (class "Default")
      (node (ref "R11") (pin "1") (pinfunction "1_1") (pintype "passive"))
      (node (ref "U13") (pin "15") (pinfunction "QA_15") (pintype "tri_state"))
      (node (ref "U14") (pin "1") (pinfunction "I1_1") (pintype "input"))
    )
    (net (code "121") (name "Net-(U13A-QB)") (class "Default")
      (node (ref "R12") (pin "1") (pinfunction "1_1") (pintype "passive"))
      (node (ref "U13") (pin "1") (pinfunction "QB_1") (pintype "tri_state"))
      (node (ref "U14") (pin "2") (pinfunction "I2_2") (pintype "input"))
    )
    (net (code "122") (name "Net-(U13A-QC)") (class "Default")
      (node (ref "R13") (pin "1") (pinfunction "1_1") (pintype "passive"))
      (node (ref "U13") (pin "2") (pinfunction "QC_2") (pintype "tri_state"))
      (node (ref "U14") (pin "3") (pinfunction "I3_3") (pintype "input"))
    )
    (net (code "123") (name "Net-(U13A-QD)") (class "Default")
      (node (ref "R14") (pin "1") (pinfunction "1_1") (pintype "passive"))
      (node (ref "U13") (pin "3") (pinfunction "QD_3") (pintype "tri_state"))
      (node (ref "U14") (pin "4") (pinfunction "I4_4") (pintype "input"))
    )
    (net (code "124") (name "Net-(U13A-QE)") (class "Default")
      (node (ref "R15") (pin "1") (pinfunction "1_1") (pintype "passive"))
      (node (ref "U13") (pin "4") (pinfunction "QE_4") (pintype "tri_state"))
      (node (ref "U14") (pin "5") (pinfunction "I5_5") (pintype "input"))
    )
    (net (code "125") (name "Net-(U13A-QF)") (class "Default")
      (node (ref "R16") (pin "1") (pinfunction "1_1") (pintype "passive"))
      (node (ref "U13") (pin "5") (pinfunction "QF_5") (pintype "tri_state"))
      (node (ref "U14") (pin "6") (pinfunction "I6_6") (pintype "input"))
    )
    (net (code "126") (name "Net-(U13A-QG)") (class "Default")
      (node (ref "R17") (pin "1") (pinfunction "1_1") (pintype "passive"))
      (node (ref "U13") (pin "6") (pinfunction "QG_6") (pintype "tri_state"))
      (node (ref "U14") (pin "7") (pinfunction "I7_7") (pintype "input"))
    )
    (net (code "127") (name "Net-(U13A-QH)") (class "Default")
      (node (ref "R18") (pin "1") (pinfunction "1_1") (pintype "passive"))
      (node (ref "U13") (pin "7") (pinfunction "QH_7") (pintype "tri_state"))
      (node (ref "U14") (pin "8") (pinfunction "I8_8") (pintype "input"))
    )
    (net (code "128") (name "OLAT") (class "Default")
      (node (ref "R21") (pin "1") (pinfunction "1_1") (pintype "passive"))
      (node (ref "U$1") (pin "PA8") (pinfunction "PA8_PA8") (pintype "bidirectional"))
      (node (ref "U11") (pin "12") (pinfunction "RCK_12") (pintype "input"))
      (node (ref "U13") (pin "12") (pinfunction "RCK_12") (pintype "input"))
    )
    (net (code "129") (name "SCK") (class "Default")
      (node (ref "JP9") (pin "3") (pinfunction "3_3") (pintype "passive"))
      (node (ref "R19") (pin "1") (pinfunction "1_1") (pintype "passive"))
      (node (ref "U$1") (pin "PB3") (pinfunction "PB3_PB3") (pintype "bidirectional"))
      (node (ref "U11") (pin "11") (pinfunction "SCK_11") (pintype "input"))
      (node (ref "U13") (pin "11") (pinfunction "SCK_11") (pintype "input"))
    )
    (net (code "130") (name "SCK2") (class "Default")
      (node (ref "U$1") (pin "PB10") (pinfunction "PB10_PB10") (pintype "bidirectional"))
      (node (ref "U1") (pin "7") (pinfunction "CLK_7") (pintype "input"))
      (node (ref "U2") (pin "7") (pinfunction "CLK_7") (pintype "input"))
    )
    (net (code "131") (name "SLNK1") (class "Default")
      (node (ref "SJ17") (pin "P$1") (pinfunction "1_P$1") (pintype "passive"))
      (node (ref "U11") (pin "9") (pinfunction "QH*_9") (pintype "tri_state"))
      (node (ref "U13") (pin "14") (pinfunction "SER_14") (pintype "input"))
    )
    (net (code "132") (name "SLNK2") (class "Default")
      (node (ref "SJ16") (pin "P$1") (pinfunction "1_P$1") (pintype "passive"))
      (node (ref "U13") (pin "9") (pinfunction "QH*_9") (pintype "tri_state"))
    )
    (net (code "133") (name "SLNK3") (class "Default")
      (node (ref "U1") (pin "13") (pinfunction "QH_13") (pintype "output"))
      (node (ref "U2") (pin "1") (pinfunction "SER_1") (pintype "input"))
    )
    (net (code "134") (name "SRV1") (class "Default")
      (node (ref "JP7") (pin "2") (pinfunction "2_2") (pintype "passive"))
      (node (ref "R25") (pin "2") (pinfunction "2_2") (pintype "passive"))
      (node (ref "U$1") (pin "PC9") (pinfunction "PC9_PC9") (pintype "bidirectional"))
    )
    (net (code "135") (name "SRV2") (class "Default")
      (node (ref "JP7") (pin "1") (pinfunction "1_1") (pintype "passive"))
      (node (ref "R24") (pin "2") (pinfunction "2_2") (pintype "passive"))
      (node (ref "U$1") (pin "PC7") (pinfunction "PC7_PC7") (pintype "bidirectional"))
    )
    (net (code "136") (name "SRV3") (class "Default")
      (node (ref "JP11") (pin "2") (pinfunction "2_2") (pintype "passive"))
      (node (ref "R26") (pin "2") (pinfunction "2_2") (pintype "passive"))
      (node (ref "U$1") (pin "PC8") (pinfunction "PC8_PC8") (pintype "bidirectional"))
    )
    (net (code "137") (name "SRV4") (class "Default")
      (node (ref "JP11") (pin "1") (pinfunction "1_1") (pintype "passive"))
      (node (ref "R27") (pin "2") (pinfunction "2_2") (pintype "passive"))
      (node (ref "U$1") (pin "PC6") (pinfunction "PC6_PC6") (pintype "bidirectional"))
    )
    (net (code "138") (name "SRV5") (class "Default")
      (node (ref "JP12") (pin "2") (pinfunction "2_2") (pintype "passive"))
      (node (ref "R64") (pin "2") (pinfunction "2_2") (pintype "passive"))
      (node (ref "U$1") (pin "PF1-PH1") (pinfunction "PF1-PH1_PF1-PH1") (pintype "bidirectional"))
    )
    (net (code "139") (name "SRV6") (class "Default")
      (node (ref "JP12") (pin "1") (pinfunction "1_1") (pintype "passive"))
      (node (ref "R65") (pin "2") (pinfunction "2_2") (pintype "passive"))
      (node (ref "U$1") (pin "PA15") (pinfunction "PA15_PA15") (pintype "bidirectional"))
    )
    (net (code "140") (name "SRV7") (class "Default")
      (node (ref "JP16") (pin "2") (pinfunction "2_2") (pintype "passive"))
      (node (ref "R66") (pin "2") (pinfunction "2_2") (pintype "passive"))
      (node (ref "U$1") (pin "PC12") (pinfunction "PC12_PC12") (pintype "bidirectional"))
    )
    (net (code "141") (name "SRV8") (class "Default")
      (node (ref "JP16") (pin "1") (pinfunction "1_1") (pintype "passive"))
      (node (ref "R67") (pin "2") (pinfunction "2_2") (pintype "passive"))
      (node (ref "U$1") (pin "PD2") (pinfunction "PD2_PD2") (pintype "bidirectional"))
    )
    (net (code "142") (name "TDRV1") (class "Default")
      (node (ref "U$1") (pin "PB12") (pinfunction "PB12_PB12") (pintype "bidirectional"))
      (node (ref "U10") (pin "12") (pinfunction "+IN_12") (pintype "input"))
      (node (ref "U6") (pin "2") (pinfunction "I_2") (pintype "input"))
    )
    (net (code "143") (name "TDRV2") (class "Default")
      (node (ref "U$1") (pin "PB2") (pinfunction "PB2_PB2") (pintype "bidirectional"))
      (node (ref "U10") (pin "3") (pinfunction "+IN_3") (pintype "input"))
      (node (ref "U6") (pin "4") (pinfunction "I_4") (pintype "input"))
    )
    (net (code "144") (name "TDRV3") (class "Default")
      (node (ref "U$1") (pin "PB15") (pinfunction "PB15_PB15") (pintype "bidirectional"))
      (node (ref "U10") (pin "10") (pinfunction "+IN_10") (pintype "input"))
      (node (ref "U5") (pin "4") (pinfunction "I_4") (pintype "input"))
    )
    (net (code "145") (name "TDRV4") (class "Default")
      (node (ref "U$1") (pin "PB1") (pinfunction "PB1_PB1") (pintype "bidirectional"))
      (node (ref "U10") (pin "5") (pinfunction "+IN_5") (pintype "input"))
      (node (ref "U5") (pin "2") (pinfunction "I_2") (pintype "input"))
    )
    (net (code "146") (name "TDRV5") (class "Default")
      (node (ref "U$1") (pin "PA0") (pinfunction "PA0_PA0") (pintype "bidirectional"))
      (node (ref "U4") (pin "2") (pinfunction "I_2") (pintype "input"))
      (node (ref "U9") (pin "12") (pinfunction "+IN_12") (pintype "input"))
    )
    (net (code "147") (name "TDRV6") (class "Default")
      (node (ref "U$1") (pin "PA4") (pinfunction "PA4_PA4") (pintype "bidirectional"))
      (node (ref "U4") (pin "4") (pinfunction "I_4") (pintype "input"))
      (node (ref "U9") (pin "3") (pinfunction "+IN_3") (pintype "input"))
    )
    (net (code "148") (name "TDRV7") (class "Default")
      (node (ref "U$1") (pin "PC3") (pinfunction "PC3_PC3") (pintype "bidirectional"))
      (node (ref "U3") (pin "4") (pinfunction "I_4") (pintype "input"))
      (node (ref "U9") (pin "10") (pinfunction "+IN_10") (pintype "input"))
    )
    (net (code "149") (name "TDRV8") (class "Default")
      (node (ref "U$1") (pin "PC0") (pinfunction "PC0_PC0") (pintype "bidirectional"))
      (node (ref "U3") (pin "2") (pinfunction "I_2") (pintype "input"))
      (node (ref "U9") (pin "5") (pinfunction "+IN_5") (pintype "input"))
    )
    (net (code "150") (name "V+") (class "Default")
      (node (ref "C1") (pin "1") (pinfunction "1_1") (pintype "passive"))
      (node (ref "C2") (pin "+") (pinfunction "+_+") (pintype "passive"))
      (node (ref "L1") (pin "1") (pinfunction "1_1") (pintype "passive"))
      (node (ref "U$1") (pin "E5V") (pinfunction "E5V_E5V") (pintype "power_in"))
      (node (ref "U8") (pin "3") (pinfunction "FB_3") (pintype "bidirectional"))
      (node (ref "U8B") (pin "1") (pinfunction "FB_1") (pintype "input"))
    )
    (net (code "151") (name "unconnected-(H1-MOUNT-PadB3,3)") (class "Default")
      (node (ref "H1") (pin "B3,3") (pinfunction "MOUNT_B3,3") (pintype "passive"))
    )
    (net (code "152") (name "unconnected-(H2-MOUNT-PadB3,3)") (class "Default")
      (node (ref "H2") (pin "B3,3") (pinfunction "MOUNT_B3,3") (pintype "passive"))
    )
    (net (code "153") (name "unconnected-(H3-MOUNT-PadB3,3)") (class "Default")
      (node (ref "H3") (pin "B3,3") (pinfunction "MOUNT_B3,3") (pintype "passive"))
    )
    (net (code "154") (name "unconnected-(H4-MOUNT-PadB3,3)") (class "Default")
      (node (ref "H4") (pin "B3,3") (pinfunction "MOUNT_B3,3") (pintype "passive"))
    )
    (net (code "155") (name "unconnected-(U$1-PadBOOT0)") (class "Default")
      (node (ref "U$1") (pin "BOOT0") (pinfunction "BOOT0_BOOT0") (pintype "bidirectional"))
    )
    (net (code "156") (name "unconnected-(U$1-PadIOREF2)") (class "Default")
      (node (ref "U$1") (pin "IOREF2") (pinfunction "IOREF2_IOREF2") (pintype "input"))
    )
    (net (code "157") (name "unconnected-(U$1-PadNC1-PF7)") (class "Default")
      (node (ref "U$1") (pin "NC1-PF7") (pinfunction "NC1-PF7_NC1-PF7") (pintype "bidirectional"))
    )
    (net (code "158") (name "unconnected-(U$1-PadNC2-PF6)") (class "Default")
      (node (ref "U$1") (pin "NC2-PF6") (pinfunction "NC2-PF6_NC2-PF6") (pintype "bidirectional"))
    )
    (net (code "159") (name "unconnected-(U$1-PadNC3)") (class "Default")
      (node (ref "U$1") (pin "NC3") (pinfunction "NC3_NC3") (pintype "no_connect"))
    )
    (net (code "160") (name "unconnected-(U$1-PadNC4)") (class "Default")
      (node (ref "U$1") (pin "NC4") (pinfunction "NC4_NC4") (pintype "no_connect"))
    )
    (net (code "161") (name "unconnected-(U$1-PadNC5-PD8)") (class "Default")
      (node (ref "U$1") (pin "NC5-PD8") (pinfunction "NC5-PD8_NC5-PD8") (pintype "bidirectional"))
    )
    (net (code "162") (name "unconnected-(U$1-PadNC6-PB11)") (class "Default")
      (node (ref "U$1") (pin "NC6-PB11") (pinfunction "NC6-PB11_NC6-PB11") (pintype "no_connect"))
    )
    (net (code "163") (name "unconnected-(U$1-PadNC7-PF5)") (class "Default")
      (node (ref "U$1") (pin "NC7-PF5") (pinfunction "NC7-PF5_NC7-PF5") (pintype "bidirectional"))
    )
    (net (code "164") (name "unconnected-(U$1-PadNC8-PF4)") (class "Default")
      (node (ref "U$1") (pin "NC8-PF4") (pinfunction "NC8-PF4_NC8-PF4") (pintype "bidirectional"))
    )
    (net (code "165") (name "unconnected-(U$1-PadNRESET)") (class "Default")
      (node (ref "U$1") (pin "NRESET") (pinfunction "NRESET_NRESET") (pintype "input"))
    )
    (net (code "166") (name "unconnected-(U$1-PadPA1)") (class "Default")
      (node (ref "U$1") (pin "PA1") (pinfunction "PA1_PA1") (pintype "bidirectional"))
    )
    (net (code "167") (name "unconnected-(U$1-PadPA2)") (class "Default")
      (node (ref "U$1") (pin "PA2") (pinfunction "PA2_PA2") (pintype "bidirectional"))
    )
    (net (code "168") (name "unconnected-(U$1-PadPA3)") (class "Default")
      (node (ref "U$1") (pin "PA3") (pinfunction "PA3_PA3") (pintype "bidirectional"))
    )
    (net (code "169") (name "unconnected-(U$1-PadPA5)") (class "Default")
      (node (ref "U$1") (pin "PA5") (pinfunction "PA5_PA5") (pintype "bidirectional"))
    )
    (net (code "170") (name "unconnected-(U$1-PadPA7)") (class "Default")
      (node (ref "U$1") (pin "PA7") (pinfunction "PA7_PA7") (pintype "bidirectional"))
    )
    (net (code "171") (name "unconnected-(U$1-PadPA9)") (class "Default")
      (node (ref "U$1") (pin "PA9") (pinfunction "PA9_PA9") (pintype "bidirectional"))
    )
    (net (code "172") (name "unconnected-(U$1-PadPA10)") (class "Default")
      (node (ref "U$1") (pin "PA10") (pinfunction "PA10_PA10") (pintype "bidirectional"))
    )
    (net (code "173") (name "unconnected-(U$1-PadPA11)") (class "Default")
      (node (ref "U$1") (pin "PA11") (pinfunction "PA11_PA11") (pintype "bidirectional"))
    )
    (net (code "174") (name "unconnected-(U$1-PadPA12)") (class "Default")
      (node (ref "U$1") (pin "PA12") (pinfunction "PA12_PA12") (pintype "bidirectional"))
    )
    (net (code "175") (name "unconnected-(U$1-PadPA13)") (class "Default")
      (node (ref "U$1") (pin "PA13") (pinfunction "PA13_PA13") (pintype "bidirectional"))
    )
    (net (code "176") (name "unconnected-(U$1-PadPA14)") (class "Default")
      (node (ref "U$1") (pin "PA14") (pinfunction "PA14_PA14") (pintype "bidirectional"))
    )
    (net (code "177") (name "unconnected-(U$1-PadPB0)") (class "Default")
      (node (ref "U$1") (pin "PB0") (pinfunction "PB0_PB0") (pintype "bidirectional"))
    )
    (net (code "178") (name "unconnected-(U$1-PadPB13)") (class "Default")
      (node (ref "U$1") (pin "PB13") (pinfunction "PB13_PB13") (pintype "bidirectional"))
    )
    (net (code "179") (name "unconnected-(U$1-PadPC1)") (class "Default")
      (node (ref "U$1") (pin "PC1") (pinfunction "PC1_PC1") (pintype "bidirectional"))
    )
    (net (code "180") (name "unconnected-(U$1-PadPC4)") (class "Default")
      (node (ref "U$1") (pin "PC4") (pinfunction "PC4_PC4") (pintype "bidirectional"))
    )
    (net (code "181") (name "unconnected-(U$1-PadPC5)") (class "Default")
      (node (ref "U$1") (pin "PC5") (pinfunction "PC5_PC5") (pintype "bidirectional"))
    )
    (net (code "182") (name "unconnected-(U$1-PadPC13)") (class "Default")
      (node (ref "U$1") (pin "PC13") (pinfunction "PC13_PC13") (pintype "bidirectional"))
    )
    (net (code "183") (name "unconnected-(U$1-PadPC14)") (class "Default")
      (node (ref "U$1") (pin "PC14") (pinfunction "PC14_PC14") (pintype "bidirectional"))
    )
    (net (code "184") (name "unconnected-(U$1-PadPC15)") (class "Default")
      (node (ref "U$1") (pin "PC15") (pinfunction "PC15_PC15") (pintype "bidirectional"))
    )
    (net (code "185") (name "unconnected-(U$1-PadPF0-PH0)") (class "Default")
      (node (ref "U$1") (pin "PF0-PH0") (pinfunction "PF0-PH0_PF0-PH0") (pintype "bidirectional"))
    )
  )
)
